# pocketbone.net
KiCad netlist of a schematic drawn in EAGLE
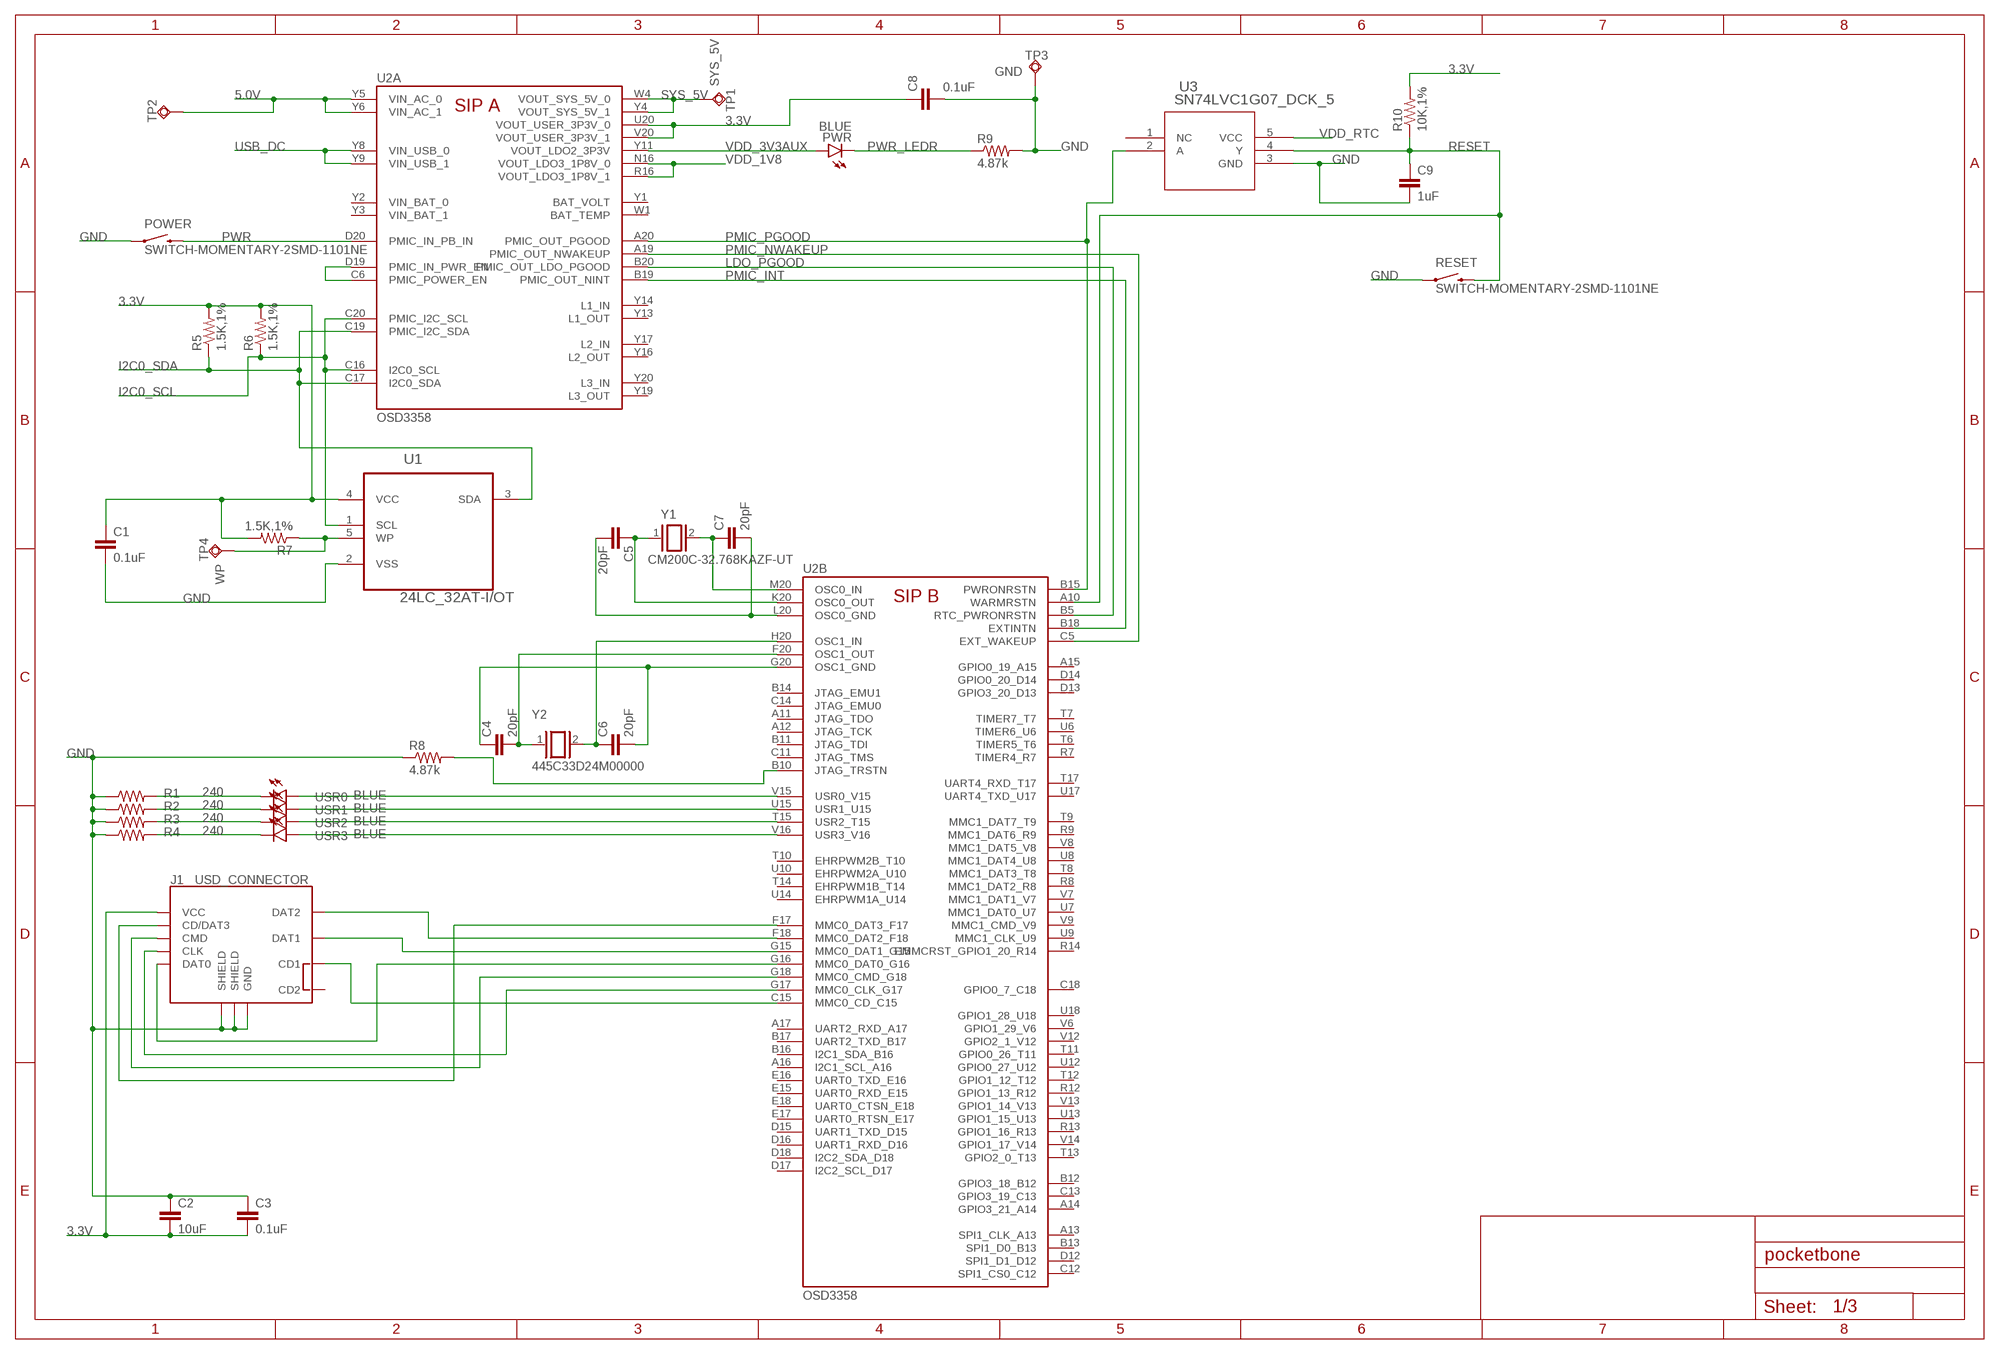
[diagram p0: schematic, sheet 1]
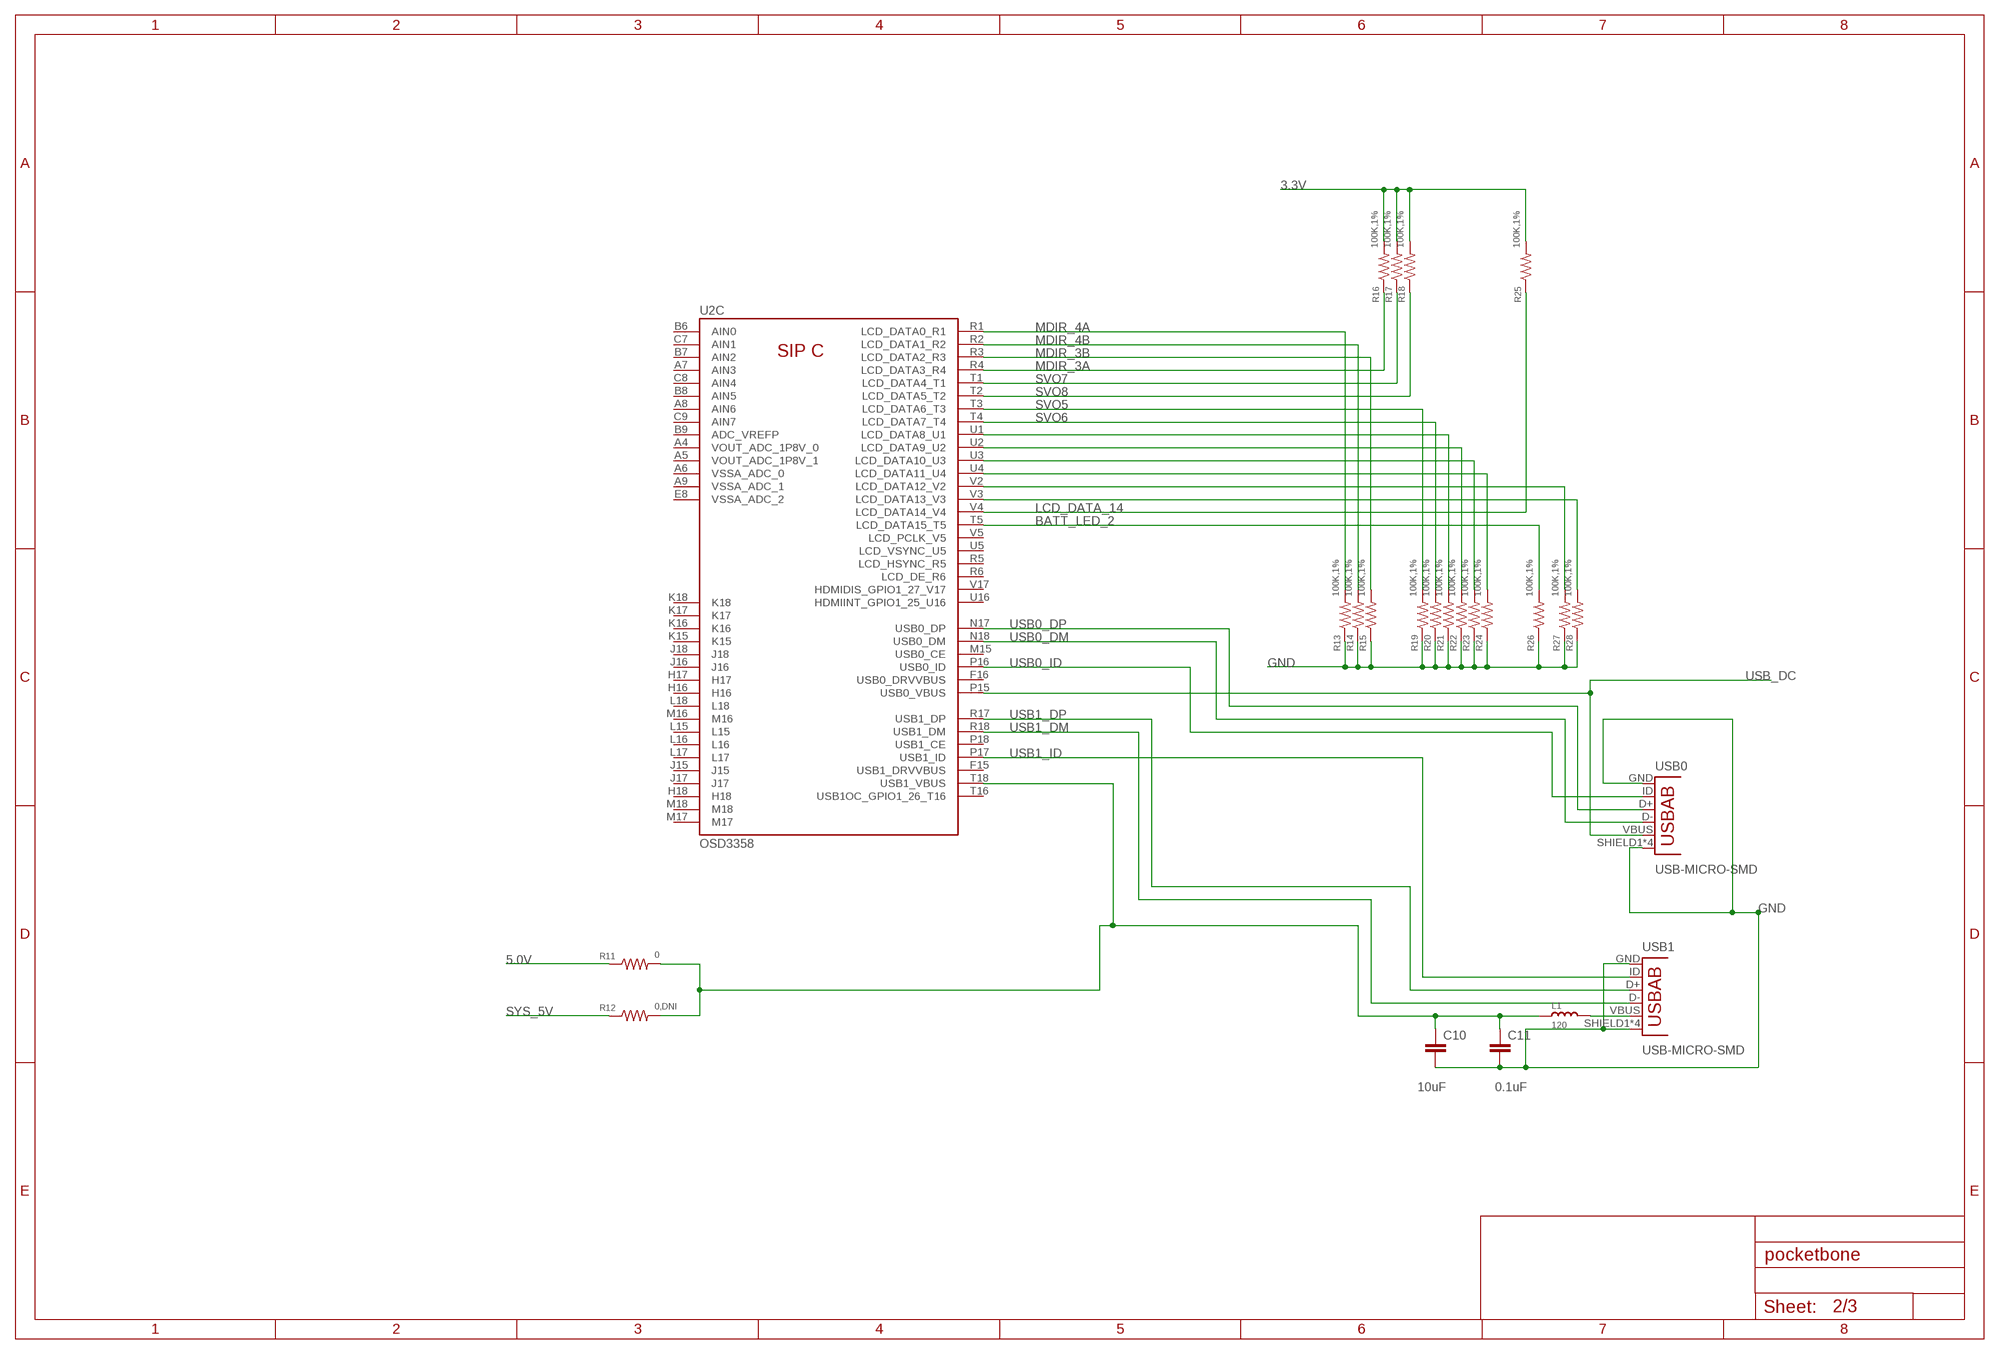
[diagram p1: schematic, sheet 2]
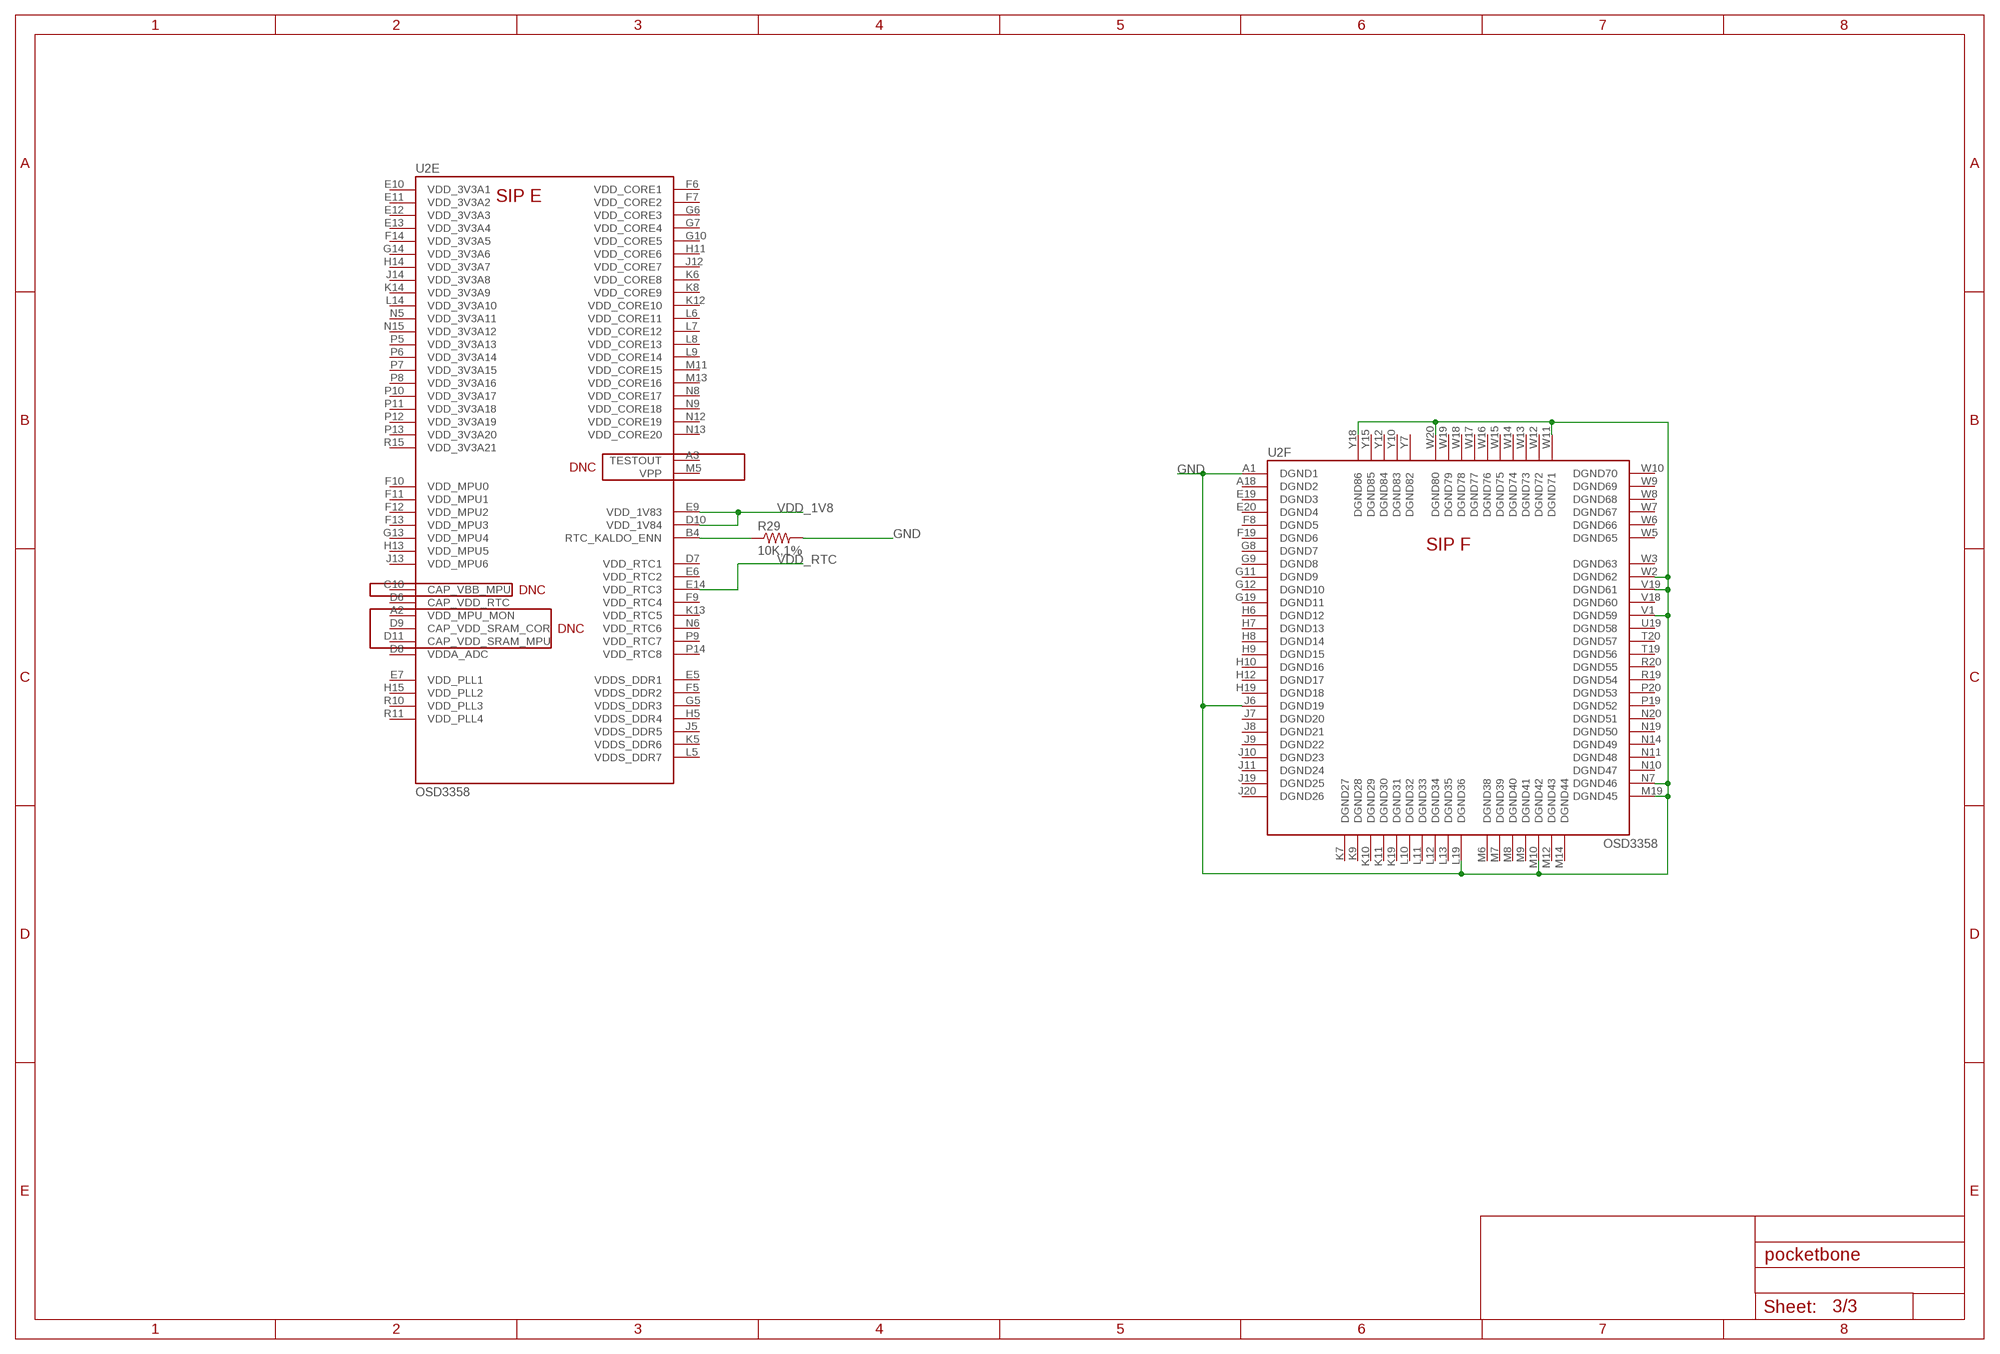
[diagram p2: schematic, sheet 3]

(export (version "E")
  (design (tool "Eeschema 10.0.6"))
  (components
    (comp (ref "C10")
      (value "10uF")
      (footprint "eagle-import:0805")
      (libsource (lib "eagle-import") (part "CAP0805"))
    )
    (comp (ref "C11")
      (value "0.1uF")
      (footprint "eagle-import:0402-CAP")
      (libsource (lib "eagle-import") (part "CAP0402-CAP"))
    )
    (comp (ref "L1")
      (value "120")
      (footprint "eagle-import:L0603")
      (libsource (lib "eagle-import") (part "INDUCTOR/FERRITE-BEAD'0603'"))
    )
    (comp (ref "R11")
      (value "0")
      (footprint "eagle-import:0402-RES")
      (libsource (lib "eagle-import") (part "RESISTOR0402-RES"))
    )
    (comp (ref "R12")
      (value "0,DNI")
      (footprint "eagle-import:0402-RES")
      (libsource (lib "eagle-import") (part "RESISTOR0402-RES"))
    )
    (comp (ref "R13")
      (value "100K,1%")
      (footprint "eagle-import:0402-RES")
      (libsource (lib "eagle-import") (part "RESISTOR0402-RES"))
    )
    (comp (ref "R14")
      (value "100K,1%")
      (footprint "eagle-import:0402-RES")
      (libsource (lib "eagle-import") (part "RESISTOR0402-RES"))
    )
    (comp (ref "R15")
      (value "100K,1%")
      (footprint "eagle-import:0402-RES")
      (libsource (lib "eagle-import") (part "RESISTOR0402-RES"))
    )
    (comp (ref "R16")
      (value "100K,1%")
      (footprint "eagle-import:0402-RES")
      (libsource (lib "eagle-import") (part "RESISTOR0402-RES"))
    )
    (comp (ref "R17")
      (value "100K,1%")
      (footprint "eagle-import:0402-RES")
      (libsource (lib "eagle-import") (part "RESISTOR0402-RES"))
    )
    (comp (ref "R18")
      (value "100K,1%")
      (footprint "eagle-import:0402-RES")
      (libsource (lib "eagle-import") (part "RESISTOR0402-RES"))
    )
    (comp (ref "R19")
      (value "100K,1%")
      (footprint "eagle-import:0402-RES")
      (libsource (lib "eagle-import") (part "RESISTOR0402-RES"))
    )
    (comp (ref "R20")
      (value "100K,1%")
      (footprint "eagle-import:0402-RES")
      (libsource (lib "eagle-import") (part "RESISTOR0402-RES"))
    )
    (comp (ref "R21")
      (value "100K,1%")
      (footprint "eagle-import:0402-RES")
      (libsource (lib "eagle-import") (part "RESISTOR0402-RES"))
    )
    (comp (ref "R22")
      (value "100K,1%")
      (footprint "eagle-import:0402-RES")
      (libsource (lib "eagle-import") (part "RESISTOR0402-RES"))
    )
    (comp (ref "R23")
      (value "100K,1%")
      (footprint "eagle-import:0402-RES")
      (libsource (lib "eagle-import") (part "RESISTOR0402-RES"))
    )
    (comp (ref "R24")
      (value "100K,1%")
      (footprint "eagle-import:0402-RES")
      (libsource (lib "eagle-import") (part "RESISTOR0402-RES"))
    )
    (comp (ref "R25")
      (value "100K,1%")
      (footprint "eagle-import:0402-RES")
      (libsource (lib "eagle-import") (part "RESISTOR0402-RES"))
    )
    (comp (ref "R26")
      (value "100K,1%")
      (footprint "eagle-import:0402-RES")
      (libsource (lib "eagle-import") (part "RESISTOR0402-RES"))
    )
    (comp (ref "R27")
      (value "100K,1%")
      (footprint "eagle-import:0402-RES")
      (libsource (lib "eagle-import") (part "RESISTOR0402-RES"))
    )
    (comp (ref "R28")
      (value "100K,1%")
      (footprint "eagle-import:0402-RES")
      (libsource (lib "eagle-import") (part "RESISTOR0402-RES"))
    )
    (comp (ref "U2")
      (value "OSD3358")
      (footprint "eagle-import:OSD3358")
      (libsource (lib "eagle-import") (part "OSD3358"))
    )
    (comp (ref "USB0")
      (value "USB-MICRO-SMD")
      (footprint "eagle-import:USB-AB-MICRO-SMD")
      (libsource (lib "eagle-import") (part "USB-AB"))
    )
    (comp (ref "USB1")
      (value "USB-MICRO-SMD")
      (footprint "eagle-import:USB-AB-MICRO-SMD")
      (libsource (lib "eagle-import") (part "USB-AB"))
    )
    (comp (ref "C1")
      (value "0.1uF")
      (footprint "eagle-import:0402-CAP")
      (libsource (lib "eagle-import") (part "CAP0402-CAP"))
    )
    (comp (ref "C2")
      (value "10uF")
      (footprint "eagle-import:0805")
      (libsource (lib "eagle-import") (part "CAP0805"))
    )
    (comp (ref "C3")
      (value "0.1uF")
      (footprint "eagle-import:0402-CAP")
      (libsource (lib "eagle-import") (part "CAP0402-CAP"))
    )
    (comp (ref "C4")
      (value "20pF")
      (footprint "eagle-import:0402-CAP")
      (libsource (lib "eagle-import") (part "CAP0402-CAP"))
    )
    (comp (ref "C5")
      (value "20pF")
      (footprint "eagle-import:0402-CAP")
      (libsource (lib "eagle-import") (part "CAP0402-CAP"))
    )
    (comp (ref "C6")
      (value "20pF")
      (footprint "eagle-import:0402-CAP")
      (libsource (lib "eagle-import") (part "CAP0402-CAP"))
    )
    (comp (ref "C7")
      (value "20pF")
      (footprint "eagle-import:0402-CAP")
      (libsource (lib "eagle-import") (part "CAP0402-CAP"))
    )
    (comp (ref "C8")
      (value "0.1uF")
      (footprint "eagle-import:0402-CAP")
      (libsource (lib "eagle-import") (part "CAP0402-CAP"))
    )
    (comp (ref "C9")
      (value "1uF")
      (footprint "eagle-import:0402-CAP")
      (libsource (lib "eagle-import") (part "CAP0402-CAP"))
    )
    (comp (ref "J1")
      (value "USD_CONNECTOR")
      (footprint "eagle-import:MICRO-SD-SOCKET-PP")
      (libsource (lib "eagle-import") (part "USD_CONNECTOR"))
    )
    (comp (ref "POWER")
      (value "SWITCH-MOMENTARY-2SMD-1101NE")
      (footprint "eagle-import:TACTILE-SWITCH-1101NE")
      (libsource (lib "eagle-import") (part "SWITCH-MOMENTARY-2SMD-1101NE"))
    )
    (comp (ref "PWR")
      (value "BLUE")
      (footprint "eagle-import:LED-0603")
      (libsource (lib "eagle-import") (part "LED0603"))
    )
    (comp (ref "R1")
      (value "240")
      (footprint "eagle-import:0402-RES")
      (libsource (lib "eagle-import") (part "RESISTOR0402-RES"))
    )
    (comp (ref "R2")
      (value "240")
      (footprint "eagle-import:0402-RES")
      (libsource (lib "eagle-import") (part "RESISTOR0402-RES"))
    )
    (comp (ref "R3")
      (value "240")
      (footprint "eagle-import:0402-RES")
      (libsource (lib "eagle-import") (part "RESISTOR0402-RES"))
    )
    (comp (ref "R4")
      (value "240")
      (footprint "eagle-import:0402-RES")
      (libsource (lib "eagle-import") (part "RESISTOR0402-RES"))
    )
    (comp (ref "R5")
      (value "1.5K,1%")
      (footprint "eagle-import:0402-RES")
      (libsource (lib "eagle-import") (part "RESISTOR0402-RES"))
    )
    (comp (ref "R6")
      (value "1.5K,1%")
      (footprint "eagle-import:0402-RES")
      (libsource (lib "eagle-import") (part "RESISTOR0402-RES"))
    )
    (comp (ref "R7")
      (value "1.5K,1%")
      (footprint "eagle-import:0402-RES")
      (libsource (lib "eagle-import") (part "RESISTOR0402-RES"))
    )
    (comp (ref "R8")
      (value "4.87k")
      (footprint "eagle-import:0402-RES")
      (libsource (lib "eagle-import") (part "RESISTOR0402-RES"))
    )
    (comp (ref "R9")
      (value "4.87k")
      (footprint "eagle-import:0402-RES")
      (libsource (lib "eagle-import") (part "RESISTOR0402-RES"))
    )
    (comp (ref "R10")
      (value "10K,1%")
      (footprint "eagle-import:0402-RES")
      (libsource (lib "eagle-import") (part "RESISTOR0402-RES"))
    )
    (comp (ref "RESET")
      (value "SWITCH-MOMENTARY-2SMD-1101NE")
      (footprint "eagle-import:TACTILE-SWITCH-1101NE")
      (libsource (lib "eagle-import") (part "SWITCH-MOMENTARY-2SMD-1101NE"))
    )
    (comp (ref "TP1")
      (value "TPSQPAD1-17")
      (footprint "eagle-import:P1-17")
      (fields (field (name "TP_SIGNAL_NAME") "SYS_5V"))
      (libsource (lib "eagle-import") (part "TPSQPAD1-17"))
    )
    (comp (ref "TP2")
      (value "TPSQPAD1-17")
      (footprint "eagle-import:P1-17")
      (fields (field (name "TP_SIGNAL_NAME") "5.0V"))
      (libsource (lib "eagle-import") (part "TPSQPAD1-17"))
    )
    (comp (ref "TP3")
      (value "TPSQPAD1-17")
      (footprint "eagle-import:P1-17")
      (fields (field (name "TP_SIGNAL_NAME") "GND"))
      (libsource (lib "eagle-import") (part "TPSQPAD1-17"))
    )
    (comp (ref "TP4")
      (value "TPSQPAD1-17")
      (footprint "eagle-import:P1-17")
      (fields (field (name "TP_SIGNAL_NAME") "WP"))
      (libsource (lib "eagle-import") (part "TPSQPAD1-17"))
    )
    (comp (ref "U1")
      (value "24LC_32AT-I/OT")
      (footprint "eagle-import:SOT95P290X145-5N")
      (fields (field (name "MPN") "24LC32AT-I/OT"))
      (libsource (lib "eagle-import") (part "24LC_32AT-I/OT"))
    )
    (comp (ref "U3")
      (value "SN74LVC1G07_DCK_5")
      (footprint "eagle-import:DCK5")
      (fields
        (field (name "GENERIC_PART_NUMBER") "SN74LVC1G07")
        (field (name "MANUFACTURER") "Texas Instruments")
        (field (name "MANUFACTURER_PART_NUMBER") "sn74lvc1g07_dck_5")
      )
      (libsource (lib "eagle-import") (part "SN74LVC1G07_DCK_5"))
    )
    (comp (ref "USR0")
      (value "BLUE")
      (footprint "eagle-import:LED-0603")
      (libsource (lib "eagle-import") (part "LED0603"))
    )
    (comp (ref "USR1")
      (value "BLUE")
      (footprint "eagle-import:LED-0603")
      (libsource (lib "eagle-import") (part "LED0603"))
    )
    (comp (ref "USR2")
      (value "BLUE")
      (footprint "eagle-import:LED-0603")
      (libsource (lib "eagle-import") (part "LED0603"))
    )
    (comp (ref "USR3")
      (value "BLUE")
      (footprint "eagle-import:LED-0603")
      (libsource (lib "eagle-import") (part "LED0603"))
    )
    (comp (ref "Y1")
      (value "CM200C-32.768KAZF-UT")
      (footprint "eagle-import:CM200C-32.768KAZF-UT")
      (libsource (lib "eagle-import") (part "CM200C-32.768KAZF-UT"))
    )
    (comp (ref "Y2")
      (value "445C33D24M00000")
      (footprint "eagle-import:445C33D24M00000")
      (libsource (lib "eagle-import") (part "445C33D24M00000"))
    )
    (comp (ref "R29")
      (value "10K,1%")
      (footprint "eagle-import:0402-RES")
      (libsource (lib "eagle-import") (part "RESISTOR0402-RES"))
    )
  )
  (nets
    (net (code "1") (name "3.3V") (class "Default")
      (node (ref "C1") (pin "1") (pinfunction "1_1") (pintype "passive"))
      (node (ref "C2") (pin "2") (pinfunction "2_2") (pintype "passive"))
      (node (ref "C3") (pin "2") (pinfunction "2_2") (pintype "passive"))
      (node (ref "C8") (pin "1") (pinfunction "1_1") (pintype "passive"))
      (node (ref "J1") (pin "VCC") (pinfunction "VCC_VCC") (pintype "bidirectional"))
      (node (ref "R10") (pin "2") (pinfunction "2_2") (pintype "passive"))
      (node (ref "R16") (pin "2") (pinfunction "2_2") (pintype "passive"))
      (node (ref "R17") (pin "2") (pinfunction "2_2") (pintype "passive"))
      (node (ref "R18") (pin "2") (pinfunction "2_2") (pintype "passive"))
      (node (ref "R25") (pin "2") (pinfunction "2_2") (pintype "passive"))
      (node (ref "R5") (pin "2") (pinfunction "2_2") (pintype "passive"))
      (node (ref "R6") (pin "2") (pinfunction "2_2") (pintype "passive"))
      (node (ref "R7") (pin "2") (pinfunction "2_2") (pintype "passive"))
      (node (ref "U1") (pin "4") (pinfunction "VCC_4") (pintype "power_in"))
      (node (ref "U2") (pin "U20") (pinfunction "VOUT_USER_3P3V_0_U20") (pintype "power_in"))
      (node (ref "U2") (pin "V20") (pinfunction "VOUT_USER_3P3V_1_V20") (pintype "power_in"))
    )
    (net (code "2") (name "5.0V") (class "Default")
      (node (ref "R11") (pin "1") (pinfunction "1_1") (pintype "passive"))
      (node (ref "TP2") (pin "TP") (pinfunction "TP_TP") (pintype "input"))
      (node (ref "U2") (pin "Y5") (pinfunction "VIN_AC_0_Y5") (pintype "power_in"))
      (node (ref "U2") (pin "Y6") (pinfunction "VIN_AC_1_Y6") (pintype "power_in"))
    )
    (net (code "3") (name "BATT_LED_2") (class "Default")
      (node (ref "R26") (pin "2") (pinfunction "2_2") (pintype "passive"))
      (node (ref "U2") (pin "T5") (pinfunction "LCD_DATA15_T5_T5") (pintype "bidirectional"))
    )
    (net (code "4") (name "GND") (class "Default")
      (node (ref "C1") (pin "2") (pinfunction "2_2") (pintype "passive"))
      (node (ref "C10") (pin "2") (pinfunction "2_2") (pintype "passive"))
      (node (ref "C11") (pin "2") (pinfunction "2_2") (pintype "passive"))
      (node (ref "C2") (pin "1") (pinfunction "1_1") (pintype "passive"))
      (node (ref "C3") (pin "1") (pinfunction "1_1") (pintype "passive"))
      (node (ref "C8") (pin "2") (pinfunction "2_2") (pintype "passive"))
      (node (ref "C9") (pin "2") (pinfunction "2_2") (pintype "passive"))
      (node (ref "J1") (pin "GND") (pinfunction "GND_GND") (pintype "bidirectional"))
      (node (ref "J1") (pin "GND1") (pinfunction "SHIELD_GND1") (pintype "bidirectional"))
      (node (ref "J1") (pin "GND3") (pinfunction "SHIELD_GND3") (pintype "bidirectional"))
      (node (ref "POWER") (pin "1") (pinfunction "1_1") (pintype "passive"))
      (node (ref "R1") (pin "1") (pinfunction "1_1") (pintype "passive"))
      (node (ref "R13") (pin "1") (pinfunction "1_1") (pintype "passive"))
      (node (ref "R14") (pin "1") (pinfunction "1_1") (pintype "passive"))
      (node (ref "R15") (pin "1") (pinfunction "1_1") (pintype "passive"))
      (node (ref "R19") (pin "1") (pinfunction "1_1") (pintype "passive"))
      (node (ref "R2") (pin "1") (pinfunction "1_1") (pintype "passive"))
      (node (ref "R20") (pin "1") (pinfunction "1_1") (pintype "passive"))
      (node (ref "R21") (pin "1") (pinfunction "1_1") (pintype "passive"))
      (node (ref "R22") (pin "1") (pinfunction "1_1") (pintype "passive"))
      (node (ref "R23") (pin "1") (pinfunction "1_1") (pintype "passive"))
      (node (ref "R24") (pin "1") (pinfunction "1_1") (pintype "passive"))
      (node (ref "R26") (pin "1") (pinfunction "1_1") (pintype "passive"))
      (node (ref "R27") (pin "1") (pinfunction "1_1") (pintype "passive"))
      (node (ref "R28") (pin "1") (pinfunction "1_1") (pintype "passive"))
      (node (ref "R29") (pin "2") (pinfunction "2_2") (pintype "passive"))
      (node (ref "R3") (pin "1") (pinfunction "1_1") (pintype "passive"))
      (node (ref "R4") (pin "1") (pinfunction "1_1") (pintype "passive"))
      (node (ref "R8") (pin "1") (pinfunction "1_1") (pintype "passive"))
      (node (ref "R9") (pin "2") (pinfunction "2_2") (pintype "passive"))
      (node (ref "RESET") (pin "1") (pinfunction "1_1") (pintype "passive"))
      (node (ref "TP3") (pin "TP") (pinfunction "TP_TP") (pintype "input"))
      (node (ref "U1") (pin "2") (pinfunction "VSS_2") (pintype "passive"))
      (node (ref "U2") (pin "A1") (pinfunction "DGND1_A1") (pintype "bidirectional"))
      (node (ref "U2") (pin "J6") (pinfunction "DGND19_J6") (pintype "bidirectional"))
      (node (ref "U2") (pin "L19") (pinfunction "DGND36_L19") (pintype "bidirectional"))
      (node (ref "U2") (pin "M10") (pinfunction "DGND42_M10") (pintype "bidirectional"))
      (node (ref "U2") (pin "M19") (pinfunction "DGND45_M19") (pintype "bidirectional"))
      (node (ref "U2") (pin "N7") (pinfunction "DGND46_N7") (pintype "bidirectional"))
      (node (ref "U2") (pin "V1") (pinfunction "DGND59_V1") (pintype "bidirectional"))
      (node (ref "U2") (pin "V19") (pinfunction "DGND61_V19") (pintype "bidirectional"))
      (node (ref "U2") (pin "W11") (pinfunction "DGND71_W11") (pintype "bidirectional"))
      (node (ref "U2") (pin "W2") (pinfunction "DGND62_W2") (pintype "bidirectional"))
      (node (ref "U2") (pin "W20") (pinfunction "DGND80_W20") (pintype "bidirectional"))
      (node (ref "U2") (pin "Y18") (pinfunction "DGND86_Y18") (pintype "bidirectional"))
      (node (ref "U3") (pin "3") (pinfunction "GND_3") (pintype "power_in"))
      (node (ref "USB0") (pin "GND") (pinfunction "GND_GND") (pintype "bidirectional"))
      (node (ref "USB0") (pin "SHIELD1") (pinfunction "SHIELD_SHIELD1") (pintype "bidirectional"))
      (node (ref "USB0") (pin "SHIELD2") (pinfunction "SHIELD_SHIELD2") (pintype "bidirectional"))
      (node (ref "USB0") (pin "SHIELD3") (pinfunction "SHIELD_SHIELD3") (pintype "bidirectional"))
      (node (ref "USB0") (pin "SHIELD4") (pinfunction "SHIELD_SHIELD4") (pintype "bidirectional"))
      (node (ref "USB1") (pin "GND") (pinfunction "GND_GND") (pintype "bidirectional"))
      (node (ref "USB1") (pin "SHIELD1") (pinfunction "SHIELD_SHIELD1") (pintype "bidirectional"))
      (node (ref "USB1") (pin "SHIELD2") (pinfunction "SHIELD_SHIELD2") (pintype "bidirectional"))
      (node (ref "USB1") (pin "SHIELD3") (pinfunction "SHIELD_SHIELD3") (pintype "bidirectional"))
      (node (ref "USB1") (pin "SHIELD4") (pinfunction "SHIELD_SHIELD4") (pintype "bidirectional"))
    )
    (net (code "5") (name "I2C0_SCL") (class "Default")
      (node (ref "R6") (pin "1") (pinfunction "1_1") (pintype "passive"))
      (node (ref "U1") (pin "1") (pinfunction "SCL_1") (pintype "input"))
      (node (ref "U2") (pin "C16") (pinfunction "I2C0_SCL_C16") (pintype "bidirectional"))
      (node (ref "U2") (pin "C20") (pinfunction "PMIC_I2C_SCL_C20") (pintype "bidirectional"))
    )
    (net (code "6") (name "I2C0_SDA") (class "Default")
      (node (ref "R5") (pin "1") (pinfunction "1_1") (pintype "passive"))
      (node (ref "U1") (pin "3") (pinfunction "SDA_3") (pintype "bidirectional"))
      (node (ref "U2") (pin "C17") (pinfunction "I2C0_SDA_C17") (pintype "bidirectional"))
      (node (ref "U2") (pin "C19") (pinfunction "PMIC_I2C_SDA_C19") (pintype "bidirectional"))
    )
    (net (code "7") (name "LCD_DATA_14") (class "Default")
      (node (ref "R25") (pin "1") (pinfunction "1_1") (pintype "passive"))
      (node (ref "U2") (pin "V4") (pinfunction "LCD_DATA14_V4_V4") (pintype "bidirectional"))
    )
    (net (code "8") (name "LDO_PGOOD") (class "Default")
      (node (ref "U2") (pin "B20") (pinfunction "PMIC_OUT_LDO_PGOOD_B20") (pintype "output"))
      (node (ref "U2") (pin "B5") (pinfunction "RTC_PWRONRSTN_B5") (pintype "bidirectional"))
    )
    (net (code "9") (name "MDIR_3A") (class "Default")
      (node (ref "R16") (pin "1") (pinfunction "1_1") (pintype "passive"))
      (node (ref "U2") (pin "R4") (pinfunction "LCD_DATA3_R4_R4") (pintype "bidirectional"))
    )
    (net (code "10") (name "MDIR_3B") (class "Default")
      (node (ref "R15") (pin "2") (pinfunction "2_2") (pintype "passive"))
      (node (ref "U2") (pin "R3") (pinfunction "LCD_DATA2_R3_R3") (pintype "bidirectional"))
    )
    (net (code "11") (name "MDIR_4A") (class "Default")
      (node (ref "R13") (pin "2") (pinfunction "2_2") (pintype "passive"))
      (node (ref "U2") (pin "R1") (pinfunction "LCD_DATA0_R1_R1") (pintype "bidirectional"))
    )
    (net (code "12") (name "MDIR_4B") (class "Default")
      (node (ref "R14") (pin "2") (pinfunction "2_2") (pintype "passive"))
      (node (ref "U2") (pin "R2") (pinfunction "LCD_DATA1_R2_R2") (pintype "bidirectional"))
    )
    (net (code "13") (name "Net-(L1-Pad2)") (class "Default")
      (node (ref "L1") (pin "2") (pinfunction "2_2") (pintype "passive"))
      (node (ref "USB1") (pin "VBUS") (pinfunction "VBUS_VBUS") (pintype "bidirectional"))
    )
    (net (code "14") (name "Net-(R1-Pad2)") (class "Default")
      (node (ref "R1") (pin "2") (pinfunction "2_2") (pintype "passive"))
      (node (ref "USR0") (pin "C") (pinfunction "C_C") (pintype "passive"))
    )
    (net (code "15") (name "Net-(R2-Pad2)") (class "Default")
      (node (ref "R2") (pin "2") (pinfunction "2_2") (pintype "passive"))
      (node (ref "USR1") (pin "C") (pinfunction "C_C") (pintype "passive"))
    )
    (net (code "16") (name "Net-(R3-Pad2)") (class "Default")
      (node (ref "R3") (pin "2") (pinfunction "2_2") (pintype "passive"))
      (node (ref "USR2") (pin "C") (pinfunction "C_C") (pintype "passive"))
    )
    (net (code "17") (name "Net-(R4-Pad2)") (class "Default")
      (node (ref "R4") (pin "2") (pinfunction "2_2") (pintype "passive"))
      (node (ref "USR3") (pin "C") (pinfunction "C_C") (pintype "passive"))
    )
    (net (code "18") (name "Net-(U1-WP)") (class "Default")
      (node (ref "R7") (pin "1") (pinfunction "1_1") (pintype "passive"))
      (node (ref "TP4") (pin "TP") (pinfunction "TP_TP") (pintype "input"))
      (node (ref "U1") (pin "5") (pinfunction "WP_5") (pintype "input"))
    )
    (net (code "19") (name "Net-(U2A-PMIC_IN_PWR_EN)") (class "Default")
      (node (ref "U2") (pin "C6") (pinfunction "PMIC_POWER_EN_C6") (pintype "output"))
      (node (ref "U2") (pin "D19") (pinfunction "PMIC_IN_PWR_EN_D19") (pintype "input"))
    )
    (net (code "20") (name "Net-(U2B-JTAG_TRSTN)") (class "Default")
      (node (ref "R8") (pin "2") (pinfunction "2_2") (pintype "passive"))
      (node (ref "U2") (pin "B10") (pinfunction "JTAG_TRSTN_B10") (pintype "bidirectional"))
    )
    (net (code "21") (name "Net-(U2B-MMC0_CD_C15)") (class "Default")
      (node (ref "J1") (pin "CD1") (pinfunction "CD1_CD1") (pintype "bidirectional"))
      (node (ref "U2") (pin "C15") (pinfunction "MMC0_CD_C15_C15") (pintype "bidirectional"))
    )
    (net (code "22") (name "Net-(U2B-MMC0_CLK_G17)") (class "Default")
      (node (ref "J1") (pin "CLK") (pinfunction "CLK_CLK") (pintype "bidirectional"))
      (node (ref "U2") (pin "G17") (pinfunction "MMC0_CLK_G17_G17") (pintype "bidirectional"))
    )
    (net (code "23") (name "Net-(U2B-MMC0_CMD_G18)") (class "Default")
      (node (ref "J1") (pin "CMD") (pinfunction "CMD_CMD") (pintype "bidirectional"))
      (node (ref "U2") (pin "G18") (pinfunction "MMC0_CMD_G18_G18") (pintype "bidirectional"))
    )
    (net (code "24") (name "Net-(U2B-MMC0_DAT0_G16)") (class "Default")
      (node (ref "J1") (pin "DAT0") (pinfunction "DAT0_DAT0") (pintype "bidirectional"))
      (node (ref "U2") (pin "G16") (pinfunction "MMC0_DAT0_G16_G16") (pintype "bidirectional"))
    )
    (net (code "25") (name "Net-(U2B-MMC0_DAT1_G15)") (class "Default")
      (node (ref "J1") (pin "DAT1") (pinfunction "DAT1_DAT1") (pintype "bidirectional"))
      (node (ref "U2") (pin "G15") (pinfunction "MMC0_DAT1_G15_G15") (pintype "bidirectional"))
    )
    (net (code "26") (name "Net-(U2B-MMC0_DAT2_F18)") (class "Default")
      (node (ref "J1") (pin "DAT2") (pinfunction "DAT2_DAT2") (pintype "bidirectional"))
      (node (ref "U2") (pin "F18") (pinfunction "MMC0_DAT2_F18_F18") (pintype "bidirectional"))
    )
    (net (code "27") (name "Net-(U2B-MMC0_DAT3_F17)") (class "Default")
      (node (ref "J1") (pin "CD/DAT3") (pinfunction "CD/DAT3_CD/DAT3") (pintype "bidirectional"))
      (node (ref "U2") (pin "F17") (pinfunction "MMC0_DAT3_F17_F17") (pintype "bidirectional"))
    )
    (net (code "28") (name "Net-(U2B-OSC0_GND)") (class "Default")
      (node (ref "C5") (pin "2") (pinfunction "2_2") (pintype "passive"))
      (node (ref "C7") (pin "2") (pinfunction "2_2") (pintype "passive"))
      (node (ref "U2") (pin "L20") (pinfunction "OSC0_GND_L20") (pintype "bidirectional"))
    )
    (net (code "29") (name "Net-(U2B-OSC0_IN)") (class "Default")
      (node (ref "C7") (pin "1") (pinfunction "1_1") (pintype "passive"))
      (node (ref "U2") (pin "M20") (pinfunction "OSC0_IN_M20") (pintype "bidirectional"))
      (node (ref "Y1") (pin "2") (pinfunction "2_2") (pintype "passive"))
    )
    (net (code "30") (name "Net-(U2B-OSC0_OUT)") (class "Default")
      (node (ref "C5") (pin "1") (pinfunction "1_1") (pintype "passive"))
      (node (ref "U2") (pin "K20") (pinfunction "OSC0_OUT_K20") (pintype "bidirectional"))
      (node (ref "Y1") (pin "1") (pinfunction "1_1") (pintype "passive"))
    )
    (net (code "31") (name "Net-(U2B-OSC1_GND)") (class "Default")
      (node (ref "C4") (pin "1") (pinfunction "1_1") (pintype "passive"))
      (node (ref "C6") (pin "2") (pinfunction "2_2") (pintype "passive"))
      (node (ref "U2") (pin "G20") (pinfunction "OSC1_GND_G20") (pintype "bidirectional"))
    )
    (net (code "32") (name "Net-(U2B-OSC1_IN)") (class "Default")
      (node (ref "C6") (pin "1") (pinfunction "1_1") (pintype "passive"))
      (node (ref "U2") (pin "H20") (pinfunction "OSC1_IN_H20") (pintype "bidirectional"))
      (node (ref "Y2") (pin "2") (pinfunction "2_2") (pintype "passive"))
    )
    (net (code "33") (name "Net-(U2B-OSC1_OUT)") (class "Default")
      (node (ref "C4") (pin "2") (pinfunction "2_2") (pintype "passive"))
      (node (ref "U2") (pin "F20") (pinfunction "OSC1_OUT_F20") (pintype "bidirectional"))
      (node (ref "Y2") (pin "1") (pinfunction "1_1") (pintype "passive"))
    )
    (net (code "34") (name "Net-(U2B-USR0_V15)") (class "Default")
      (node (ref "U2") (pin "V15") (pinfunction "USR0_V15_V15") (pintype "bidirectional"))
      (node (ref "USR0") (pin "A") (pinfunction "A_A") (pintype "passive"))
    )
    (net (code "35") (name "Net-(U2B-USR1_U15)") (class "Default")
      (node (ref "U2") (pin "U15") (pinfunction "USR1_U15_U15") (pintype "bidirectional"))
      (node (ref "USR1") (pin "A") (pinfunction "A_A") (pintype "passive"))
    )
    (net (code "36") (name "Net-(U2B-USR2_T15)") (class "Default")
      (node (ref "U2") (pin "T15") (pinfunction "USR2_T15_T15") (pintype "bidirectional"))
      (node (ref "USR2") (pin "A") (pinfunction "A_A") (pintype "passive"))
    )
    (net (code "37") (name "Net-(U2B-USR3_V16)") (class "Default")
      (node (ref "U2") (pin "V16") (pinfunction "USR3_V16_V16") (pintype "bidirectional"))
      (node (ref "USR3") (pin "A") (pinfunction "A_A") (pintype "passive"))
    )
    (net (code "38") (name "Net-(U2C-LCD_DATA8_U1)") (class "Default")
      (node (ref "R21") (pin "2") (pinfunction "2_2") (pintype "passive"))
      (node (ref "U2") (pin "U1") (pinfunction "LCD_DATA8_U1_U1") (pintype "bidirectional"))
    )
    (net (code "39") (name "Net-(U2C-LCD_DATA9_U2)") (class "Default")
      (node (ref "R22") (pin "2") (pinfunction "2_2") (pintype "passive"))
      (node (ref "U2") (pin "U2") (pinfunction "LCD_DATA9_U2_U2") (pintype "bidirectional"))
    )
    (net (code "40") (name "Net-(U2C-LCD_DATA10_U3)") (class "Default")
      (node (ref "R23") (pin "2") (pinfunction "2_2") (pintype "passive"))
      (node (ref "U2") (pin "U3") (pinfunction "LCD_DATA10_U3_U3") (pintype "bidirectional"))
    )
    (net (code "41") (name "Net-(U2C-LCD_DATA11_U4)") (class "Default")
      (node (ref "R24") (pin "2") (pinfunction "2_2") (pintype "passive"))
      (node (ref "U2") (pin "U4") (pinfunction "LCD_DATA11_U4_U4") (pintype "bidirectional"))
    )
    (net (code "42") (name "Net-(U2C-LCD_DATA12_V2)") (class "Default")
      (node (ref "R27") (pin "2") (pinfunction "2_2") (pintype "passive"))
      (node (ref "U2") (pin "V2") (pinfunction "LCD_DATA12_V2_V2") (pintype "bidirectional"))
    )
    (net (code "43") (name "Net-(U2C-LCD_DATA13_V3)") (class "Default")
      (node (ref "R28") (pin "2") (pinfunction "2_2") (pintype "passive"))
      (node (ref "U2") (pin "V3") (pinfunction "LCD_DATA13_V3_V3") (pintype "bidirectional"))
    )
    (net (code "44") (name "Net-(U2C-USB1_VBUS)") (class "Default")
      (node (ref "C10") (pin "1") (pinfunction "1_1") (pintype "passive"))
      (node (ref "C11") (pin "1") (pinfunction "1_1") (pintype "passive"))
      (node (ref "L1") (pin "1") (pinfunction "1_1") (pintype "passive"))
      (node (ref "R11") (pin "2") (pinfunction "2_2") (pintype "passive"))
      (node (ref "R12") (pin "2") (pinfunction "2_2") (pintype "passive"))
      (node (ref "U2") (pin "T18") (pinfunction "USB1_VBUS_T18") (pintype "bidirectional"))
    )
    (net (code "45") (name "Net-(U2E-RTC_KALDO_ENN)") (class "Default")
      (node (ref "R29") (pin "1") (pinfunction "1_1") (pintype "passive"))
      (node (ref "U2") (pin "B4") (pinfunction "RTC_KALDO_ENN_B4") (pintype "bidirectional"))
    )
    (net (code "46") (name "PMIC_INT") (class "Default")
      (node (ref "U2") (pin "B18") (pinfunction "EXTINTN_B18") (pintype "bidirectional"))
      (node (ref "U2") (pin "B19") (pinfunction "PMIC_OUT_NINT_B19") (pintype "output"))
    )
    (net (code "47") (name "PMIC_NWAKEUP") (class "Default")
      (node (ref "U2") (pin "A19") (pinfunction "PMIC_OUT_NWAKEUP_A19") (pintype "output"))
      (node (ref "U2") (pin "C5") (pinfunction "EXT_WAKEUP_C5") (pintype "bidirectional"))
    )
    (net (code "48") (name "PMIC_PGOOD") (class "Default")
      (node (ref "U2") (pin "A20") (pinfunction "PMIC_OUT_PGOOD_A20") (pintype "output"))
      (node (ref "U2") (pin "B15") (pinfunction "PWRONRSTN_B15") (pintype "bidirectional"))
      (node (ref "U3") (pin "2") (pinfunction "A_2") (pintype "input"))
    )
    (net (code "49") (name "PWR") (class "Default")
      (node (ref "POWER") (pin "2") (pinfunction "2_2") (pintype "passive"))
      (node (ref "U2") (pin "D20") (pinfunction "PMIC_IN_PB_IN_D20") (pintype "bidirectional"))
    )
    (net (code "50") (name "PWR_LEDR") (class "Default")
      (node (ref "PWR") (pin "C") (pinfunction "C_C") (pintype "passive"))
      (node (ref "R9") (pin "1") (pinfunction "1_1") (pintype "passive"))
    )
    (net (code "51") (name "RESET") (class "Default")
      (node (ref "C9") (pin "1") (pinfunction "1_1") (pintype "passive"))
      (node (ref "R10") (pin "1") (pinfunction "1_1") (pintype "passive"))
      (node (ref "RESET") (pin "2") (pinfunction "2_2") (pintype "passive"))
      (node (ref "U2") (pin "A10") (pinfunction "WARMRSTN_A10") (pintype "bidirectional"))
      (node (ref "U3") (pin "4") (pinfunction "Y_4") (pintype "output"))
    )
    (net (code "52") (name "SVO5") (class "Default")
      (node (ref "R19") (pin "2") (pinfunction "2_2") (pintype "passive"))
      (node (ref "U2") (pin "T3") (pinfunction "LCD_DATA6_T3_T3") (pintype "bidirectional"))
    )
    (net (code "53") (name "SVO6") (class "Default")
      (node (ref "R20") (pin "2") (pinfunction "2_2") (pintype "passive"))
      (node (ref "U2") (pin "T4") (pinfunction "LCD_DATA7_T4_T4") (pintype "bidirectional"))
    )
    (net (code "54") (name "SVO7") (class "Default")
      (node (ref "R17") (pin "1") (pinfunction "1_1") (pintype "passive"))
      (node (ref "U2") (pin "T1") (pinfunction "LCD_DATA4_T1_T1") (pintype "bidirectional"))
    )
    (net (code "55") (name "SVO8") (class "Default")
      (node (ref "R18") (pin "1") (pinfunction "1_1") (pintype "passive"))
      (node (ref "U2") (pin "T2") (pinfunction "LCD_DATA5_T2_T2") (pintype "bidirectional"))
    )
    (net (code "56") (name "SYS_5V") (class "Default")
      (node (ref "R12") (pin "1") (pinfunction "1_1") (pintype "passive"))
      (node (ref "TP1") (pin "TP") (pinfunction "TP_TP") (pintype "input"))
      (node (ref "U2") (pin "W4") (pinfunction "VOUT_SYS_5V_0_W4") (pintype "power_in"))
      (node (ref "U2") (pin "Y4") (pinfunction "VOUT_SYS_5V_1_Y4") (pintype "power_in"))
    )
    (net (code "57") (name "USB0_DM") (class "Default")
      (node (ref "U2") (pin "N18") (pinfunction "USB0_DM_N18") (pintype "bidirectional"))
      (node (ref "USB0") (pin "D-") (pinfunction "D-_D-") (pintype "bidirectional"))
    )
    (net (code "58") (name "USB0_DP") (class "Default")
      (node (ref "U2") (pin "N17") (pinfunction "USB0_DP_N17") (pintype "bidirectional"))
      (node (ref "USB0") (pin "D+") (pinfunction "D+_D+") (pintype "bidirectional"))
    )
    (net (code "59") (name "USB0_ID") (class "Default")
      (node (ref "U2") (pin "P16") (pinfunction "USB0_ID_P16") (pintype "bidirectional"))
      (node (ref "USB0") (pin "ID") (pinfunction "USBID_ID") (pintype "bidirectional"))
    )
    (net (code "60") (name "USB1_DM") (class "Default")
      (node (ref "U2") (pin "R18") (pinfunction "USB1_DM_R18") (pintype "bidirectional"))
      (node (ref "USB1") (pin "D-") (pinfunction "D-_D-") (pintype "bidirectional"))
    )
    (net (code "61") (name "USB1_DP") (class "Default")
      (node (ref "U2") (pin "R17") (pinfunction "USB1_DP_R17") (pintype "bidirectional"))
      (node (ref "USB1") (pin "D+") (pinfunction "D+_D+") (pintype "bidirectional"))
    )
    (net (code "62") (name "USB1_ID") (class "Default")
      (node (ref "U2") (pin "P17") (pinfunction "USB1_ID_P17") (pintype "bidirectional"))
      (node (ref "USB1") (pin "ID") (pinfunction "USBID_ID") (pintype "bidirectional"))
    )
    (net (code "63") (name "USB_DC") (class "Default")
      (node (ref "U2") (pin "P15") (pinfunction "USB0_VBUS_P15") (pintype "bidirectional"))
      (node (ref "U2") (pin "Y8") (pinfunction "VIN_USB_0_Y8") (pintype "power_in"))
      (node (ref "U2") (pin "Y9") (pinfunction "VIN_USB_1_Y9") (pintype "power_in"))
      (node (ref "USB0") (pin "VBUS") (pinfunction "VBUS_VBUS") (pintype "bidirectional"))
    )
    (net (code "64") (name "VDD_1V8") (class "Default")
      (node (ref "U2") (pin "D10") (pinfunction "VDD_1V84_D10") (pintype "bidirectional"))
      (node (ref "U2") (pin "E9") (pinfunction "VDD_1V83_E9") (pintype "bidirectional"))
      (node (ref "U2") (pin "N16") (pinfunction "VOUT_LDO3_1P8V_0_N16") (pintype "power_in"))
      (node (ref "U2") (pin "R16") (pinfunction "VOUT_LDO3_1P8V_1_R16") (pintype "power_in"))
    )
    (net (code "65") (name "VDD_3V3AUX") (class "Default")
      (node (ref "PWR") (pin "A") (pinfunction "A_A") (pintype "passive"))
      (node (ref "U2") (pin "Y11") (pinfunction "VOUT_LDO2_3P3V_Y11") (pintype "power_in"))
    )
    (net (code "66") (name "VDD_RTC") (class "Default")
      (node (ref "U2") (pin "E14") (pinfunction "VDD_RTC3_E14") (pintype "bidirectional"))
      (node (ref "U3") (pin "5") (pinfunction "VCC_5") (pintype "power_in"))
    )
    (net (code "67") (name "VIN_BAT_0") (class "Default")
      (node (ref "U2") (pin "Y2") (pinfunction "VIN_BAT_0_Y2") (pintype "power_in"))
    )
    (net (code "68") (name "VIN_BAT_1") (class "Default")
      (node (ref "U2") (pin "Y3") (pinfunction "VIN_BAT_1_Y3") (pintype "power_in"))
    )
    (net (code "69") (name "unconnected-(J1-PadCD2)") (class "Default")
      (node (ref "J1") (pin "CD2") (pinfunction "CD2_CD2") (pintype "bidirectional"))
    )
    (net (code "70") (name "unconnected-(U2-PadH16)") (class "Default")
      (node (ref "U2") (pin "H16") (pinfunction "H16_H16") (pintype "bidirectional"))
    )
    (net (code "71") (name "unconnected-(U2-PadH17)") (class "Default")
      (node (ref "U2") (pin "H17") (pinfunction "H17_H17") (pintype "bidirectional"))
    )
    (net (code "72") (name "unconnected-(U2-PadH18)") (class "Default")
      (node (ref "U2") (pin "H18") (pinfunction "H18_H18") (pintype "bidirectional"))
    )
    (net (code "73") (name "unconnected-(U2-PadJ15)") (class "Default")
      (node (ref "U2") (pin "J15") (pinfunction "J15_J15") (pintype "bidirectional"))
    )
    (net (code "74") (name "unconnected-(U2-PadJ16)") (class "Default")
      (node (ref "U2") (pin "J16") (pinfunction "J16_J16") (pintype "bidirectional"))
    )
    (net (code "75") (name "unconnected-(U2-PadJ17)") (class "Default")
      (node (ref "U2") (pin "J17") (pinfunction "J17_J17") (pintype "bidirectional"))
    )
    (net (code "76") (name "unconnected-(U2-PadJ18)") (class "Default")
      (node (ref "U2") (pin "J18") (pinfunction "J18_J18") (pintype "bidirectional"))
    )
    (net (code "77") (name "unconnected-(U2-PadK15)") (class "Default")
      (node (ref "U2") (pin "K15") (pinfunction "K15_K15") (pintype "bidirectional"))
    )
    (net (code "78") (name "unconnected-(U2-PadK16)") (class "Default")
      (node (ref "U2") (pin "K16") (pinfunction "K16_K16") (pintype "bidirectional"))
    )
    (net (code "79") (name "unconnected-(U2-PadK17)") (class "Default")
      (node (ref "U2") (pin "K17") (pinfunction "K17_K17") (pintype "bidirectional"))
    )
    (net (code "80") (name "unconnected-(U2-PadK18)") (class "Default")
      (node (ref "U2") (pin "K18") (pinfunction "K18_K18") (pintype "bidirectional"))
    )
    (net (code "81") (name "unconnected-(U2-PadL15)") (class "Default")
      (node (ref "U2") (pin "L15") (pinfunction "L15_L15") (pintype "bidirectional"))
    )
    (net (code "82") (name "unconnected-(U2-PadL16)") (class "Default")
      (node (ref "U2") (pin "L16") (pinfunction "L16_L16") (pintype "bidirectional"))
    )
    (net (code "83") (name "unconnected-(U2-PadL17)") (class "Default")
      (node (ref "U2") (pin "L17") (pinfunction "L17_L17") (pintype "bidirectional"))
    )
    (net (code "84") (name "unconnected-(U2-PadL18)") (class "Default")
      (node (ref "U2") (pin "L18") (pinfunction "L18_L18") (pintype "bidirectional"))
    )
    (net (code "85") (name "unconnected-(U2-PadM16)") (class "Default")
      (node (ref "U2") (pin "M16") (pinfunction "M16_M16") (pintype "bidirectional"))
    )
    (net (code "86") (name "unconnected-(U2-PadM17)") (class "Default")
      (node (ref "U2") (pin "M17") (pinfunction "M17_M17") (pintype "bidirectional"))
    )
    (net (code "87") (name "unconnected-(U2-PadM18)") (class "Default")
      (node (ref "U2") (pin "M18") (pinfunction "M18_M18") (pintype "bidirectional"))
    )
    (net (code "88") (name "unconnected-(U2A-BAT_TEMP-PadW1)") (class "Default")
      (node (ref "U2") (pin "W1") (pinfunction "BAT_TEMP_W1") (pintype "bidirectional"))
    )
    (net (code "89") (name "unconnected-(U2A-BAT_VOLT-PadY1)") (class "Default")
      (node (ref "U2") (pin "Y1") (pinfunction "BAT_VOLT_Y1") (pintype "bidirectional"))
    )
    (net (code "90") (name "unconnected-(U2A-L1_IN-PadY14)") (class "Default")
      (node (ref "U2") (pin "Y14") (pinfunction "L1_IN_Y14") (pintype "bidirectional"))
    )
    (net (code "91") (name "unconnected-(U2A-L1_OUT-PadY13)") (class "Default")
      (node (ref "U2") (pin "Y13") (pinfunction "L1_OUT_Y13") (pintype "bidirectional"))
    )
    (net (code "92") (name "unconnected-(U2A-L2_IN-PadY17)") (class "Default")
      (node (ref "U2") (pin "Y17") (pinfunction "L2_IN_Y17") (pintype "bidirectional"))
    )
    (net (code "93") (name "unconnected-(U2A-L2_OUT-PadY16)") (class "Default")
      (node (ref "U2") (pin "Y16") (pinfunction "L2_OUT_Y16") (pintype "bidirectional"))
    )
    (net (code "94") (name "unconnected-(U2A-L3_IN-PadY20)") (class "Default")
      (node (ref "U2") (pin "Y20") (pinfunction "L3_IN_Y20") (pintype "bidirectional"))
    )
    (net (code "95") (name "unconnected-(U2A-L3_OUT-PadY19)") (class "Default")
      (node (ref "U2") (pin "Y19") (pinfunction "L3_OUT_Y19") (pintype "bidirectional"))
    )
    (net (code "96") (name "unconnected-(U2B-EHRPWM1A_U14-PadU14)") (class "Default")
      (node (ref "U2") (pin "U14") (pinfunction "EHRPWM1A_U14_U14") (pintype "bidirectional"))
    )
    (net (code "97") (name "unconnected-(U2B-EHRPWM1B_T14-PadT14)") (class "Default")
      (node (ref "U2") (pin "T14") (pinfunction "EHRPWM1B_T14_T14") (pintype "bidirectional"))
    )
    (net (code "98") (name "unconnected-(U2B-EHRPWM2A_U10-PadU10)") (class "Default")
      (node (ref "U2") (pin "U10") (pinfunction "EHRPWM2A_U10_U10") (pintype "bidirectional"))
    )
    (net (code "99") (name "unconnected-(U2B-EHRPWM2B_T10-PadT10)") (class "Default")
      (node (ref "U2") (pin "T10") (pinfunction "EHRPWM2B_T10_T10") (pintype "bidirectional"))
    )
    (net (code "100") (name "unconnected-(U2B-EMMCRST_GPIO1_20_R14-PadR14)") (class "Default")
      (node (ref "U2") (pin "R14") (pinfunction "EMMCRST_GPIO1_20_R14_R14") (pintype "bidirectional"))
    )
    (net (code "101") (name "unconnected-(U2B-GPIO0_7_C18-PadC18)") (class "Default")
      (node (ref "U2") (pin "C18") (pinfunction "GPIO0_7_C18_C18") (pintype "bidirectional"))
    )
    (net (code "102") (name "unconnected-(U2B-GPIO0_19_A15-PadA15)") (class "Default")
      (node (ref "U2") (pin "A15") (pinfunction "GPIO0_19_A15_A15") (pintype "bidirectional"))
    )
    (net (code "103") (name "unconnected-(U2B-GPIO0_20_D14-PadD14)") (class "Default")
      (node (ref "U2") (pin "D14") (pinfunction "GPIO0_20_D14_D14") (pintype "bidirectional"))
    )
    (net (code "104") (name "unconnected-(U2B-GPIO0_26_T11-PadT11)") (class "Default")
      (node (ref "U2") (pin "T11") (pinfunction "GPIO0_26_T11_T11") (pintype "bidirectional"))
    )
    (net (code "105") (name "unconnected-(U2B-GPIO0_27_U12-PadU12)") (class "Default")
      (node (ref "U2") (pin "U12") (pinfunction "GPIO0_27_U12_U12") (pintype "bidirectional"))
    )
    (net (code "106") (name "unconnected-(U2B-GPIO1_12_T12-PadT12)") (class "Default")
      (node (ref "U2") (pin "T12") (pinfunction "GPIO1_12_T12_T12") (pintype "bidirectional"))
    )
    (net (code "107") (name "unconnected-(U2B-GPIO1_13_R12-PadR12)") (class "Default")
      (node (ref "U2") (pin "R12") (pinfunction "GPIO1_13_R12_R12") (pintype "bidirectional"))
    )
    (net (code "108") (name "unconnected-(U2B-GPIO1_14_V13-PadV13)") (class "Default")
      (node (ref "U2") (pin "V13") (pinfunction "GPIO1_14_V13_V13") (pintype "bidirectional"))
    )
    (net (code "109") (name "unconnected-(U2B-GPIO1_15_U13-PadU13)") (class "Default")
      (node (ref "U2") (pin "U13") (pinfunction "GPIO1_15_U13_U13") (pintype "bidirectional"))
    )
    (net (code "110") (name "unconnected-(U2B-GPIO1_16_R13-PadR13)") (class "Default")
      (node (ref "U2") (pin "R13") (pinfunction "GPIO1_16_R13_R13") (pintype "bidirectional"))
    )
    (net (code "111") (name "unconnected-(U2B-GPIO1_17_V14-PadV14)") (class "Default")
      (node (ref "U2") (pin "V14") (pinfunction "GPIO1_17_V14_V14") (pintype "bidirectional"))
    )
    (net (code "112") (name "unconnected-(U2B-GPIO1_28_U18-PadU18)") (class "Default")
      (node (ref "U2") (pin "U18") (pinfunction "GPIO1_28_U18_U18") (pintype "bidirectional"))
    )
    (net (code "113") (name "unconnected-(U2B-GPIO1_29_V6-PadV6)") (class "Default")
      (node (ref "U2") (pin "V6") (pinfunction "GPIO1_29_V6_V6") (pintype "bidirectional"))
    )
    (net (code "114") (name "unconnected-(U2B-GPIO2_0_T13-PadT13)") (class "Default")
      (node (ref "U2") (pin "T13") (pinfunction "GPIO2_0_T13_T13") (pintype "bidirectional"))
    )
    (net (code "115") (name "unconnected-(U2B-GPIO2_1_V12-PadV12)") (class "Default")
      (node (ref "U2") (pin "V12") (pinfunction "GPIO2_1_V12_V12") (pintype "bidirectional"))
    )
    (net (code "116") (name "unconnected-(U2B-GPIO3_18_B12-PadB12)") (class "Default")
      (node (ref "U2") (pin "B12") (pinfunction "GPIO3_18_B12_B12") (pintype "bidirectional"))
    )
    (net (code "117") (name "unconnected-(U2B-GPIO3_19_C13-PadC13)") (class "Default")
      (node (ref "U2") (pin "C13") (pinfunction "GPIO3_19_C13_C13") (pintype "bidirectional"))
    )
    (net (code "118") (name "unconnected-(U2B-GPIO3_20_D13-PadD13)") (class "Default")
      (node (ref "U2") (pin "D13") (pinfunction "GPIO3_20_D13_D13") (pintype "bidirectional"))
    )
    (net (code "119") (name "unconnected-(U2B-GPIO3_21_A14-PadA14)") (class "Default")
      (node (ref "U2") (pin "A14") (pinfunction "GPIO3_21_A14_A14") (pintype "bidirectional"))
    )
    (net (code "120") (name "unconnected-(U2B-I2C1_SCL_A16-PadA16)") (class "Default")
      (node (ref "U2") (pin "A16") (pinfunction "I2C1_SCL_A16_A16") (pintype "bidirectional"))
    )
    (net (code "121") (name "unconnected-(U2B-I2C1_SDA_B16-PadB16)") (class "Default")
      (node (ref "U2") (pin "B16") (pinfunction "I2C1_SDA_B16_B16") (pintype "bidirectional"))
    )
    (net (code "122") (name "unconnected-(U2B-I2C2_SCL_D17-PadD17)") (class "Default")
      (node (ref "U2") (pin "D17") (pinfunction "I2C2_SCL_D17_D17") (pintype "bidirectional"))
    )
    (net (code "123") (name "unconnected-(U2B-I2C2_SDA_D18-PadD18)") (class "Default")
      (node (ref "U2") (pin "D18") (pinfunction "I2C2_SDA_D18_D18") (pintype "bidirectional"))
    )
    (net (code "124") (name "unconnected-(U2B-JTAG_EMU0-PadC14)") (class "Default")
      (node (ref "U2") (pin "C14") (pinfunction "JTAG_EMU0_C14") (pintype "bidirectional"))
    )
    (net (code "125") (name "unconnected-(U2B-JTAG_EMU1-PadB14)") (class "Default")
      (node (ref "U2") (pin "B14") (pinfunction "JTAG_EMU1_B14") (pintype "bidirectional"))
    )
    (net (code "126") (name "unconnected-(U2B-JTAG_TCK-PadA12)") (class "Default")
      (node (ref "U2") (pin "A12") (pinfunction "JTAG_TCK_A12") (pintype "bidirectional"))
    )
    (net (code "127") (name "unconnected-(U2B-JTAG_TDI-PadB11)") (class "Default")
      (node (ref "U2") (pin "B11") (pinfunction "JTAG_TDI_B11") (pintype "bidirectional"))
    )
    (net (code "128") (name "unconnected-(U2B-JTAG_TDO-PadA11)") (class "Default")
      (node (ref "U2") (pin "A11") (pinfunction "JTAG_TDO_A11") (pintype "bidirectional"))
    )
    (net (code "129") (name "unconnected-(U2B-JTAG_TMS-PadC11)") (class "Default")
      (node (ref "U2") (pin "C11") (pinfunction "JTAG_TMS_C11") (pintype "bidirectional"))
    )
    (net (code "130") (name "unconnected-(U2B-MMC1_CLK_U9-PadU9)") (class "Default")
      (node (ref "U2") (pin "U9") (pinfunction "MMC1_CLK_U9_U9") (pintype "bidirectional"))
    )
    (net (code "131") (name "unconnected-(U2B-MMC1_CMD_V9-PadV9)") (class "Default")
      (node (ref "U2") (pin "V9") (pinfunction "MMC1_CMD_V9_V9") (pintype "bidirectional"))
    )
    (net (code "132") (name "unconnected-(U2B-MMC1_DAT0_U7-PadU7)") (class "Default")
      (node (ref "U2") (pin "U7") (pinfunction "MMC1_DAT0_U7_U7") (pintype "bidirectional"))
    )
    (net (code "133") (name "unconnected-(U2B-MMC1_DAT1_V7-PadV7)") (class "Default")
      (node (ref "U2") (pin "V7") (pinfunction "MMC1_DAT1_V7_V7") (pintype "bidirectional"))
    )
    (net (code "134") (name "unconnected-(U2B-MMC1_DAT2_R8-PadR8)") (class "Default")
      (node (ref "U2") (pin "R8") (pinfunction "MMC1_DAT2_R8_R8") (pintype "bidirectional"))
    )
    (net (code "135") (name "unconnected-(U2B-MMC1_DAT3_T8-PadT8)") (class "Default")
      (node (ref "U2") (pin "T8") (pinfunction "MMC1_DAT3_T8_T8") (pintype "bidirectional"))
    )
    (net (code "136") (name "unconnected-(U2B-MMC1_DAT4_U8-PadU8)") (class "Default")
      (node (ref "U2") (pin "U8") (pinfunction "MMC1_DAT4_U8_U8") (pintype "bidirectional"))
    )
    (net (code "137") (name "unconnected-(U2B-MMC1_DAT5_V8-PadV8)") (class "Default")
      (node (ref "U2") (pin "V8") (pinfunction "MMC1_DAT5_V8_V8") (pintype "bidirectional"))
    )
    (net (code "138") (name "unconnected-(U2B-MMC1_DAT6_R9-PadR9)") (class "Default")
      (node (ref "U2") (pin "R9") (pinfunction "MMC1_DAT6_R9_R9") (pintype "bidirectional"))
    )
    (net (code "139") (name "unconnected-(U2B-MMC1_DAT7_T9-PadT9)") (class "Default")
      (node (ref "U2") (pin "T9") (pinfunction "MMC1_DAT7_T9_T9") (pintype "bidirectional"))
    )
    (net (code "140") (name "unconnected-(U2B-SPI1_CLK_A13-PadA13)") (class "Default")
      (node (ref "U2") (pin "A13") (pinfunction "SPI1_CLK_A13_A13") (pintype "bidirectional"))
    )
    (net (code "141") (name "unconnected-(U2B-SPI1_CS0_C12-PadC12)") (class "Default")
      (node (ref "U2") (pin "C12") (pinfunction "SPI1_CS0_C12_C12") (pintype "bidirectional"))
    )
    (net (code "142") (name "unconnected-(U2B-SPI1_D0_B13-PadB13)") (class "Default")
      (node (ref "U2") (pin "B13") (pinfunction "SPI1_D0_B13_B13") (pintype "bidirectional"))
    )
    (net (code "143") (name "unconnected-(U2B-SPI1_D1_D12-PadD12)") (class "Default")
      (node (ref "U2") (pin "D12") (pinfunction "SPI1_D1_D12_D12") (pintype "bidirectional"))
    )
    (net (code "144") (name "unconnected-(U2B-TIMER4_R7-PadR7)") (class "Default")
      (node (ref "U2") (pin "R7") (pinfunction "TIMER4_R7_R7") (pintype "bidirectional"))
    )
    (net (code "145") (name "unconnected-(U2B-TIMER5_T6-PadT6)") (class "Default")
      (node (ref "U2") (pin "T6") (pinfunction "TIMER5_T6_T6") (pintype "bidirectional"))
    )
    (net (code "146") (name "unconnected-(U2B-TIMER6_U6-PadU6)") (class "Default")
      (node (ref "U2") (pin "U6") (pinfunction "TIMER6_U6_U6") (pintype "bidirectional"))
    )
    (net (code "147") (name "unconnected-(U2B-TIMER7_T7-PadT7)") (class "Default")
      (node (ref "U2") (pin "T7") (pinfunction "TIMER7_T7_T7") (pintype "bidirectional"))
    )
    (net (code "148") (name "unconnected-(U2B-UART0_CTSN_E18-PadE18)") (class "Default")
      (node (ref "U2") (pin "E18") (pinfunction "UART0_CTSN_E18_E18") (pintype "bidirectional"))
    )
    (net (code "149") (name "unconnected-(U2B-UART0_RTSN_E17-PadE17)") (class "Default")
      (node (ref "U2") (pin "E17") (pinfunction "UART0_RTSN_E17_E17") (pintype "bidirectional"))
    )
    (net (code "150") (name "unconnected-(U2B-UART0_RXD_E15-PadE15)") (class "Default")
      (node (ref "U2") (pin "E15") (pinfunction "UART0_RXD_E15_E15") (pintype "bidirectional"))
    )
    (net (code "151") (name "unconnected-(U2B-UART0_TXD_E16-PadE16)") (class "Default")
      (node (ref "U2") (pin "E16") (pinfunction "UART0_TXD_E16_E16") (pintype "bidirectional"))
    )
    (net (code "152") (name "unconnected-(U2B-UART1_RXD_D16-PadD16)") (class "Default")
      (node (ref "U2") (pin "D16") (pinfunction "UART1_RXD_D16_D16") (pintype "bidirectional"))
    )
    (net (code "153") (name "unconnected-(U2B-UART1_TXD_D15-PadD15)") (class "Default")
      (node (ref "U2") (pin "D15") (pinfunction "UART1_TXD_D15_D15") (pintype "bidirectional"))
    )
    (net (code "154") (name "unconnected-(U2B-UART2_RXD_A17-PadA17)") (class "Default")
      (node (ref "U2") (pin "A17") (pinfunction "UART2_RXD_A17_A17") (pintype "bidirectional"))
    )
    (net (code "155") (name "unconnected-(U2B-UART2_TXD_B17-PadB17)") (class "Default")
      (node (ref "U2") (pin "B17") (pinfunction "UART2_TXD_B17_B17") (pintype "bidirectional"))
    )
    (net (code "156") (name "unconnected-(U2B-UART4_RXD_T17-PadT17)") (class "Default")
      (node (ref "U2") (pin "T17") (pinfunction "UART4_RXD_T17_T17") (pintype "bidirectional"))
    )
    (net (code "157") (name "unconnected-(U2B-UART4_TXD_U17-PadU17)") (class "Default")
      (node (ref "U2") (pin "U17") (pinfunction "UART4_TXD_U17_U17") (pintype "bidirectional"))
    )
    (net (code "158") (name "unconnected-(U2C-ADC_VREFP-PadB9)") (class "Default")
      (node (ref "U2") (pin "B9") (pinfunction "ADC_VREFP_B9") (pintype "bidirectional"))
    )
    (net (code "159") (name "unconnected-(U2C-AIN0-PadB6)") (class "Default")
      (node (ref "U2") (pin "B6") (pinfunction "AIN0_B6") (pintype "bidirectional"))
    )
    (net (code "160") (name "unconnected-(U2C-AIN1-PadC7)") (class "Default")
      (node (ref "U2") (pin "C7") (pinfunction "AIN1_C7") (pintype "bidirectional"))
    )
    (net (code "161") (name "unconnected-(U2C-AIN2-PadB7)") (class "Default")
      (node (ref "U2") (pin "B7") (pinfunction "AIN2_B7") (pintype "bidirectional"))
    )
    (net (code "162") (name "unconnected-(U2C-AIN3-PadA7)") (class "Default")
      (node (ref "U2") (pin "A7") (pinfunction "AIN3_A7") (pintype "bidirectional"))
    )
    (net (code "163") (name "unconnected-(U2C-AIN4-PadC8)") (class "Default")
      (node (ref "U2") (pin "C8") (pinfunction "AIN4_C8") (pintype "bidirectional"))
    )
    (net (code "164") (name "unconnected-(U2C-AIN5-PadB8)") (class "Default")
      (node (ref "U2") (pin "B8") (pinfunction "AIN5_B8") (pintype "bidirectional"))
    )
    (net (code "165") (name "unconnected-(U2C-AIN6-PadA8)") (class "Default")
      (node (ref "U2") (pin "A8") (pinfunction "AIN6_A8") (pintype "bidirectional"))
    )
    (net (code "166") (name "unconnected-(U2C-AIN7-PadC9)") (class "Default")
      (node (ref "U2") (pin "C9") (pinfunction "AIN7_C9") (pintype "bidirectional"))
    )
    (net (code "167") (name "unconnected-(U2C-HDMIDIS_GPIO1_27_V17-PadV17)") (class "Default")
      (node (ref "U2") (pin "V17") (pinfunction "HDMIDIS_GPIO1_27_V17_V17") (pintype "bidirectional"))
    )
    (net (code "168") (name "unconnected-(U2C-HDMIINT_GPIO1_25_U16-PadU16)") (class "Default")
      (node (ref "U2") (pin "U16") (pinfunction "HDMIINT_GPIO1_25_U16_U16") (pintype "bidirectional"))
    )
    (net (code "169") (name "unconnected-(U2C-LCD_DE_R6-PadR6)") (class "Default")
      (node (ref "U2") (pin "R6") (pinfunction "LCD_DE_R6_R6") (pintype "bidirectional"))
    )
    (net (code "170") (name "unconnected-(U2C-LCD_HSYNC_R5-PadR5)") (class "Default")
      (node (ref "U2") (pin "R5") (pinfunction "LCD_HSYNC_R5_R5") (pintype "bidirectional"))
    )
    (net (code "171") (name "unconnected-(U2C-LCD_PCLK_V5-PadV5)") (class "Default")
      (node (ref "U2") (pin "V5") (pinfunction "LCD_PCLK_V5_V5") (pintype "bidirectional"))
    )
    (net (code "172") (name "unconnected-(U2C-LCD_VSYNC_U5-PadU5)") (class "Default")
      (node (ref "U2") (pin "U5") (pinfunction "LCD_VSYNC_U5_U5") (pintype "bidirectional"))
    )
    (net (code "173") (name "unconnected-(U2C-USB0_CE-PadM15)") (class "Default")
      (node (ref "U2") (pin "M15") (pinfunction "USB0_CE_M15") (pintype "bidirectional"))
    )
    (net (code "174") (name "unconnected-(U2C-USB0_DRVVBUS-PadF16)") (class "Default")
      (node (ref "U2") (pin "F16") (pinfunction "USB0_DRVVBUS_F16") (pintype "bidirectional"))
    )
    (net (code "175") (name "unconnected-(U2C-USB1OC_GPIO1_26_T16-PadT16)") (class "Default")
      (node (ref "U2") (pin "T16") (pinfunction "USB1OC_GPIO1_26_T16_T16") (pintype "bidirectional"))
    )
    (net (code "176") (name "unconnected-(U2C-USB1_CE-PadP18)") (class "Default")
      (node (ref "U2") (pin "P18") (pinfunction "USB1_CE_P18") (pintype "bidirectional"))
    )
    (net (code "177") (name "unconnected-(U2C-USB1_DRVVBUS-PadF15)") (class "Default")
      (node (ref "U2") (pin "F15") (pinfunction "USB1_DRVVBUS_F15") (pintype "bidirectional"))
    )
    (net (code "178") (name "unconnected-(U2C-VOUT_ADC_1P8V_0-PadA4)") (class "Default")
      (node (ref "U2") (pin "A4") (pinfunction "VOUT_ADC_1P8V_0_A4") (pintype "bidirectional"))
    )
    (net (code "179") (name "unconnected-(U2C-VOUT_ADC_1P8V_1-PadA5)") (class "Default")
      (node (ref "U2") (pin "A5") (pinfunction "VOUT_ADC_1P8V_1_A5") (pintype "bidirectional"))
    )
    (net (code "180") (name "unconnected-(U2C-VSSA_ADC_0-PadA6)") (class "Default")
      (node (ref "U2") (pin "A6") (pinfunction "VSSA_ADC_0_A6") (pintype "bidirectional"))
    )
    (net (code "181") (name "unconnected-(U2C-VSSA_ADC_1-PadA9)") (class "Default")
      (node (ref "U2") (pin "A9") (pinfunction "VSSA_ADC_1_A9") (pintype "bidirectional"))
    )
    (net (code "182") (name "unconnected-(U2C-VSSA_ADC_2-PadE8)") (class "Default")
      (node (ref "U2") (pin "E8") (pinfunction "VSSA_ADC_2_E8") (pintype "bidirectional"))
    )
    (net (code "183") (name "unconnected-(U2E-CAP_VBB_MPU-PadC10)") (class "Default")
      (node (ref "U2") (pin "C10") (pinfunction "CAP_VBB_MPU_C10") (pintype "bidirectional"))
    )
    (net (code "184") (name "unconnected-(U2E-CAP_VDD_RTC-PadD6)") (class "Default")
      (node (ref "U2") (pin "D6") (pinfunction "CAP_VDD_RTC_D6") (pintype "bidirectional"))
    )
    (net (code "185") (name "unconnected-(U2E-CAP_VDD_SRAM_COR-PadD9)") (class "Default")
      (node (ref "U2") (pin "D9") (pinfunction "CAP_VDD_SRAM_COR_D9") (pintype "bidirectional"))
    )
    (net (code "186") (name "unconnected-(U2E-CAP_VDD_SRAM_MPU-PadD11)") (class "Default")
      (node (ref "U2") (pin "D11") (pinfunction "CAP_VDD_SRAM_MPU_D11") (pintype "bidirectional"))
    )
    (net (code "187") (name "unconnected-(U2E-TESTOUT-PadA3)") (class "Default")
      (node (ref "U2") (pin "A3") (pinfunction "TESTOUT_A3") (pintype "bidirectional"))
    )
    (net (code "188") (name "unconnected-(U2E-VDDA_ADC-PadD8)") (class "Default")
      (node (ref "U2") (pin "D8") (pinfunction "VDDA_ADC_D8") (pintype "bidirectional"))
    )
    (net (code "189") (name "unconnected-(U2E-VDDS_DDR1-PadE5)") (class "Default")
      (node (ref "U2") (pin "E5") (pinfunction "VDDS_DDR1_E5") (pintype "bidirectional"))
    )
    (net (code "190") (name "unconnected-(U2E-VDDS_DDR2-PadF5)") (class "Default")
      (node (ref "U2") (pin "F5") (pinfunction "VDDS_DDR2_F5") (pintype "bidirectional"))
    )
    (net (code "191") (name "unconnected-(U2E-VDDS_DDR3-PadG5)") (class "Default")
      (node (ref "U2") (pin "G5") (pinfunction "VDDS_DDR3_G5") (pintype "bidirectional"))
    )
    (net (code "192") (name "unconnected-(U2E-VDDS_DDR4-PadH5)") (class "Default")
      (node (ref "U2") (pin "H5") (pinfunction "VDDS_DDR4_H5") (pintype "bidirectional"))
    )
    (net (code "193") (name "unconnected-(U2E-VDDS_DDR5-PadJ5)") (class "Default")
      (node (ref "U2") (pin "J5") (pinfunction "VDDS_DDR5_J5") (pintype "bidirectional"))
    )
    (net (code "194") (name "unconnected-(U2E-VDDS_DDR6-PadK5)") (class "Default")
      (node (ref "U2") (pin "K5") (pinfunction "VDDS_DDR6_K5") (pintype "bidirectional"))
    )
    (net (code "195") (name "unconnected-(U2E-VDDS_DDR7-PadL5)") (class "Default")
      (node (ref "U2") (pin "L5") (pinfunction "VDDS_DDR7_L5") (pintype "bidirectional"))
    )
    (net (code "196") (name "unconnected-(U2E-VDD_3V3A1-PadE10)") (class "Default")
      (node (ref "U2") (pin "E10") (pinfunction "VDD_3V3A1_E10") (pintype "bidirectional"))
    )
    (net (code "197") (name "unconnected-(U2E-VDD_3V3A2-PadE11)") (class "Default")
      (node (ref "U2") (pin "E11") (pinfunction "VDD_3V3A2_E11") (pintype "bidirectional"))
    )
    (net (code "198") (name "unconnected-(U2E-VDD_3V3A3-PadE12)") (class "Default")
      (node (ref "U2") (pin "E12") (pinfunction "VDD_3V3A3_E12") (pintype "bidirectional"))
    )
    (net (code "199") (name "unconnected-(U2E-VDD_3V3A4-PadE13)") (class "Default")
      (node (ref "U2") (pin "E13") (pinfunction "VDD_3V3A4_E13") (pintype "bidirectional"))
    )
    (net (code "200") (name "unconnected-(U2E-VDD_3V3A5-PadF14)") (class "Default")
      (node (ref "U2") (pin "F14") (pinfunction "VDD_3V3A5_F14") (pintype "bidirectional"))
    )
    (net (code "201") (name "unconnected-(U2E-VDD_3V3A6-PadG14)") (class "Default")
      (node (ref "U2") (pin "G14") (pinfunction "VDD_3V3A6_G14") (pintype "bidirectional"))
    )
    (net (code "202") (name "unconnected-(U2E-VDD_3V3A7-PadH14)") (class "Default")
      (node (ref "U2") (pin "H14") (pinfunction "VDD_3V3A7_H14") (pintype "bidirectional"))
    )
    (net (code "203") (name "unconnected-(U2E-VDD_3V3A8-PadJ14)") (class "Default")
      (node (ref "U2") (pin "J14") (pinfunction "VDD_3V3A8_J14") (pintype "bidirectional"))
    )
    (net (code "204") (name "unconnected-(U2E-VDD_3V3A9-PadK14)") (class "Default")
      (node (ref "U2") (pin "K14") (pinfunction "VDD_3V3A9_K14") (pintype "bidirectional"))
    )
    (net (code "205") (name "unconnected-(U2E-VDD_3V3A10-PadL14)") (class "Default")
      (node (ref "U2") (pin "L14") (pinfunction "VDD_3V3A10_L14") (pintype "bidirectional"))
    )
    (net (code "206") (name "unconnected-(U2E-VDD_3V3A11-PadN5)") (class "Default")
      (node (ref "U2") (pin "N5") (pinfunction "VDD_3V3A11_N5") (pintype "bidirectional"))
    )
    (net (code "207") (name "unconnected-(U2E-VDD_3V3A12-PadN15)") (class "Default")
      (node (ref "U2") (pin "N15") (pinfunction "VDD_3V3A12_N15") (pintype "bidirectional"))
    )
    (net (code "208") (name "unconnected-(U2E-VDD_3V3A13-PadP5)") (class "Default")
      (node (ref "U2") (pin "P5") (pinfunction "VDD_3V3A13_P5") (pintype "bidirectional"))
    )
    (net (code "209") (name "unconnected-(U2E-VDD_3V3A14-PadP6)") (class "Default")
      (node (ref "U2") (pin "P6") (pinfunction "VDD_3V3A14_P6") (pintype "bidirectional"))
    )
    (net (code "210") (name "unconnected-(U2E-VDD_3V3A15-PadP7)") (class "Default")
      (node (ref "U2") (pin "P7") (pinfunction "VDD_3V3A15_P7") (pintype "bidirectional"))
    )
    (net (code "211") (name "unconnected-(U2E-VDD_3V3A16-PadP8)") (class "Default")
      (node (ref "U2") (pin "P8") (pinfunction "VDD_3V3A16_P8") (pintype "bidirectional"))
    )
    (net (code "212") (name "unconnected-(U2E-VDD_3V3A17-PadP10)") (class "Default")
      (node (ref "U2") (pin "P10") (pinfunction "VDD_3V3A17_P10") (pintype "bidirectional"))
    )
    (net (code "213") (name "unconnected-(U2E-VDD_3V3A18-PadP11)") (class "Default")
      (node (ref "U2") (pin "P11") (pinfunction "VDD_3V3A18_P11") (pintype "bidirectional"))
    )
    (net (code "214") (name "unconnected-(U2E-VDD_3V3A19-PadP12)") (class "Default")
      (node (ref "U2") (pin "P12") (pinfunction "VDD_3V3A19_P12") (pintype "bidirectional"))
    )
    (net (code "215") (name "unconnected-(U2E-VDD_3V3A20-PadP13)") (class "Default")
      (node (ref "U2") (pin "P13") (pinfunction "VDD_3V3A20_P13") (pintype "bidirectional"))
    )
    (net (code "216") (name "unconnected-(U2E-VDD_3V3A21-PadR15)") (class "Default")
      (node (ref "U2") (pin "R15") (pinfunction "VDD_3V3A21_R15") (pintype "bidirectional"))
    )
    (net (code "217") (name "unconnected-(U2E-VDD_CORE1-PadF6)") (class "Default")
      (node (ref "U2") (pin "F6") (pinfunction "VDD_CORE1_F6") (pintype "bidirectional"))
    )
    (net (code "218") (name "unconnected-(U2E-VDD_CORE2-PadF7)") (class "Default")
      (node (ref "U2") (pin "F7") (pinfunction "VDD_CORE2_F7") (pintype "bidirectional"))
    )
    (net (code "219") (name "unconnected-(U2E-VDD_CORE3-PadG6)") (class "Default")
      (node (ref "U2") (pin "G6") (pinfunction "VDD_CORE3_G6") (pintype "bidirectional"))
    )
    (net (code "220") (name "unconnected-(U2E-VDD_CORE4-PadG7)") (class "Default")
      (node (ref "U2") (pin "G7") (pinfunction "VDD_CORE4_G7") (pintype "bidirectional"))
    )
    (net (code "221") (name "unconnected-(U2E-VDD_CORE5-PadG10)") (class "Default")
      (node (ref "U2") (pin "G10") (pinfunction "VDD_CORE5_G10") (pintype "bidirectional"))
    )
    (net (code "222") (name "unconnected-(U2E-VDD_CORE6-PadH11)") (class "Default")
      (node (ref "U2") (pin "H11") (pinfunction "VDD_CORE6_H11") (pintype "bidirectional"))
    )
    (net (code "223") (name "unconnected-(U2E-VDD_CORE7-PadJ12)") (class "Default")
      (node (ref "U2") (pin "J12") (pinfunction "VDD_CORE7_J12") (pintype "bidirectional"))
    )
    (net (code "224") (name "unconnected-(U2E-VDD_CORE8-PadK6)") (class "Default")
      (node (ref "U2") (pin "K6") (pinfunction "VDD_CORE8_K6") (pintype "bidirectional"))
    )
    (net (code "225") (name "unconnected-(U2E-VDD_CORE9-PadK8)") (class "Default")
      (node (ref "U2") (pin "K8") (pinfunction "VDD_CORE9_K8") (pintype "bidirectional"))
    )
    (net (code "226") (name "unconnected-(U2E-VDD_CORE10-PadK12)") (class "Default")
      (node (ref "U2") (pin "K12") (pinfunction "VDD_CORE10_K12") (pintype "bidirectional"))
    )
    (net (code "227") (name "unconnected-(U2E-VDD_CORE11-PadL6)") (class "Default")
      (node (ref "U2") (pin "L6") (pinfunction "VDD_CORE11_L6") (pintype "bidirectional"))
    )
    (net (code "228") (name "unconnected-(U2E-VDD_CORE12-PadL7)") (class "Default")
      (node (ref "U2") (pin "L7") (pinfunction "VDD_CORE12_L7") (pintype "bidirectional"))
    )
    (net (code "229") (name "unconnected-(U2E-VDD_CORE13-PadL8)") (class "Default")
      (node (ref "U2") (pin "L8") (pinfunction "VDD_CORE13_L8") (pintype "bidirectional"))
    )
    (net (code "230") (name "unconnected-(U2E-VDD_CORE14-PadL9)") (class "Default")
      (node (ref "U2") (pin "L9") (pinfunction "VDD_CORE14_L9") (pintype "bidirectional"))
    )
    (net (code "231") (name "unconnected-(U2E-VDD_CORE15-PadM11)") (class "Default")
      (node (ref "U2") (pin "M11") (pinfunction "VDD_CORE15_M11") (pintype "bidirectional"))
    )
    (net (code "232") (name "unconnected-(U2E-VDD_CORE16-PadM13)") (class "Default")
      (node (ref "U2") (pin "M13") (pinfunction "VDD_CORE16_M13") (pintype "bidirectional"))
    )
    (net (code "233") (name "unconnected-(U2E-VDD_CORE17-PadN8)") (class "Default")
      (node (ref "U2") (pin "N8") (pinfunction "VDD_CORE17_N8") (pintype "bidirectional"))
    )
    (net (code "234") (name "unconnected-(U2E-VDD_CORE18-PadN9)") (class "Default")
      (node (ref "U2") (pin "N9") (pinfunction "VDD_CORE18_N9") (pintype "bidirectional"))
    )
    (net (code "235") (name "unconnected-(U2E-VDD_CORE19-PadN12)") (class "Default")
      (node (ref "U2") (pin "N12") (pinfunction "VDD_CORE19_N12") (pintype "bidirectional"))
    )
    (net (code "236") (name "unconnected-(U2E-VDD_CORE20-PadN13)") (class "Default")
      (node (ref "U2") (pin "N13") (pinfunction "VDD_CORE20_N13") (pintype "bidirectional"))
    )
    (net (code "237") (name "unconnected-(U2E-VDD_MPU0-PadF10)") (class "Default")
      (node (ref "U2") (pin "F10") (pinfunction "VDD_MPU0_F10") (pintype "bidirectional"))
    )
    (net (code "238") (name "unconnected-(U2E-VDD_MPU1-PadF11)") (class "Default")
      (node (ref "U2") (pin "F11") (pinfunction "VDD_MPU1_F11") (pintype "bidirectional"))
    )
    (net (code "239") (name "unconnected-(U2E-VDD_MPU2-PadF12)") (class "Default")
      (node (ref "U2") (pin "F12") (pinfunction "VDD_MPU2_F12") (pintype "bidirectional"))
    )
    (net (code "240") (name "unconnected-(U2E-VDD_MPU3-PadF13)") (class "Default")
      (node (ref "U2") (pin "F13") (pinfunction "VDD_MPU3_F13") (pintype "bidirectional"))
    )
    (net (code "241") (name "unconnected-(U2E-VDD_MPU4-PadG13)") (class "Default")
      (node (ref "U2") (pin "G13") (pinfunction "VDD_MPU4_G13") (pintype "bidirectional"))
    )
    (net (code "242") (name "unconnected-(U2E-VDD_MPU5-PadH13)") (class "Default")
      (node (ref "U2") (pin "H13") (pinfunction "VDD_MPU5_H13") (pintype "bidirectional"))
    )
    (net (code "243") (name "unconnected-(U2E-VDD_MPU6-PadJ13)") (class "Default")
      (node (ref "U2") (pin "J13") (pinfunction "VDD_MPU6_J13") (pintype "bidirectional"))
    )
    (net (code "244") (name "unconnected-(U2E-VDD_MPU_MON-PadA2)") (class "Default")
      (node (ref "U2") (pin "A2") (pinfunction "VDD_MPU_MON_A2") (pintype "bidirectional"))
    )
    (net (code "245") (name "unconnected-(U2E-VDD_PLL1-PadE7)") (class "Default")
      (node (ref "U2") (pin "E7") (pinfunction "VDD_PLL1_E7") (pintype "bidirectional"))
    )
    (net (code "246") (name "unconnected-(U2E-VDD_PLL2-PadH15)") (class "Default")
      (node (ref "U2") (pin "H15") (pinfunction "VDD_PLL2_H15") (pintype "bidirectional"))
    )
    (net (code "247") (name "unconnected-(U2E-VDD_PLL3-PadR10)") (class "Default")
      (node (ref "U2") (pin "R10") (pinfunction "VDD_PLL3_R10") (pintype "bidirectional"))
    )
    (net (code "248") (name "unconnected-(U2E-VDD_PLL4-PadR11)") (class "Default")
      (node (ref "U2") (pin "R11") (pinfunction "VDD_PLL4_R11") (pintype "bidirectional"))
    )
    (net (code "249") (name "unconnected-(U2E-VDD_RTC1-PadD7)") (class "Default")
      (node (ref "U2") (pin "D7") (pinfunction "VDD_RTC1_D7") (pintype "bidirectional"))
    )
    (net (code "250") (name "unconnected-(U2E-VDD_RTC2-PadE6)") (class "Default")
      (node (ref "U2") (pin "E6") (pinfunction "VDD_RTC2_E6") (pintype "bidirectional"))
    )
    (net (code "251") (name "unconnected-(U2E-VDD_RTC4-PadF9)") (class "Default")
      (node (ref "U2") (pin "F9") (pinfunction "VDD_RTC4_F9") (pintype "bidirectional"))
    )
    (net (code "252") (name "unconnected-(U2E-VDD_RTC5-PadK13)") (class "Default")
      (node (ref "U2") (pin "K13") (pinfunction "VDD_RTC5_K13") (pintype "bidirectional"))
    )
    (net (code "253") (name "unconnected-(U2E-VDD_RTC6-PadN6)") (class "Default")
      (node (ref "U2") (pin "N6") (pinfunction "VDD_RTC6_N6") (pintype "bidirectional"))
    )
    (net (code "254") (name "unconnected-(U2E-VDD_RTC7-PadP9)") (class "Default")
      (node (ref "U2") (pin "P9") (pinfunction "VDD_RTC7_P9") (pintype "bidirectional"))
    )
    (net (code "255") (name "unconnected-(U2E-VDD_RTC8-PadP14)") (class "Default")
      (node (ref "U2") (pin "P14") (pinfunction "VDD_RTC8_P14") (pintype "bidirectional"))
    )
    (net (code "256") (name "unconnected-(U2E-VPP-PadM5)") (class "Default")
      (node (ref "U2") (pin "M5") (pinfunction "VPP_M5") (pintype "bidirectional"))
    )
    (net (code "257") (name "unconnected-(U2F-DGND2-PadA18)") (class "Default")
      (node (ref "U2") (pin "A18") (pinfunction "DGND2_A18") (pintype "bidirectional"))
    )
    (net (code "258") (name "unconnected-(U2F-DGND3-PadE19)") (class "Default")
      (node (ref "U2") (pin "E19") (pinfunction "DGND3_E19") (pintype "bidirectional"))
    )
    (net (code "259") (name "unconnected-(U2F-DGND4-PadE20)") (class "Default")
      (node (ref "U2") (pin "E20") (pinfunction "DGND4_E20") (pintype "bidirectional"))
    )
    (net (code "260") (name "unconnected-(U2F-DGND5-PadF8)") (class "Default")
      (node (ref "U2") (pin "F8") (pinfunction "DGND5_F8") (pintype "bidirectional"))
    )
    (net (code "261") (name "unconnected-(U2F-DGND6-PadF19)") (class "Default")
      (node (ref "U2") (pin "F19") (pinfunction "DGND6_F19") (pintype "bidirectional"))
    )
    (net (code "262") (name "unconnected-(U2F-DGND7-PadG8)") (class "Default")
      (node (ref "U2") (pin "G8") (pinfunction "DGND7_G8") (pintype "bidirectional"))
    )
    (net (code "263") (name "unconnected-(U2F-DGND8-PadG9)") (class "Default")
      (node (ref "U2") (pin "G9") (pinfunction "DGND8_G9") (pintype "bidirectional"))
    )
    (net (code "264") (name "unconnected-(U2F-DGND9-PadG11)") (class "Default")
      (node (ref "U2") (pin "G11") (pinfunction "DGND9_G11") (pintype "bidirectional"))
    )
    (net (code "265") (name "unconnected-(U2F-DGND10-PadG12)") (class "Default")
      (node (ref "U2") (pin "G12") (pinfunction "DGND10_G12") (pintype "bidirectional"))
    )
    (net (code "266") (name "unconnected-(U2F-DGND11-PadG19)") (class "Default")
      (node (ref "U2") (pin "G19") (pinfunction "DGND11_G19") (pintype "bidirectional"))
    )
    (net (code "267") (name "unconnected-(U2F-DGND12-PadH6)") (class "Default")
      (node (ref "U2") (pin "H6") (pinfunction "DGND12_H6") (pintype "bidirectional"))
    )
    (net (code "268") (name "unconnected-(U2F-DGND13-PadH7)") (class "Default")
      (node (ref "U2") (pin "H7") (pinfunction "DGND13_H7") (pintype "bidirectional"))
    )
    (net (code "269") (name "unconnected-(U2F-DGND14-PadH8)") (class "Default")
      (node (ref "U2") (pin "H8") (pinfunction "DGND14_H8") (pintype "bidirectional"))
    )
    (net (code "270") (name "unconnected-(U2F-DGND15-PadH9)") (class "Default")
      (node (ref "U2") (pin "H9") (pinfunction "DGND15_H9") (pintype "bidirectional"))
    )
    (net (code "271") (name "unconnected-(U2F-DGND16-PadH10)") (class "Default")
      (node (ref "U2") (pin "H10") (pinfunction "DGND16_H10") (pintype "bidirectional"))
    )
    (net (code "272") (name "unconnected-(U2F-DGND17-PadH12)") (class "Default")
      (node (ref "U2") (pin "H12") (pinfunction "DGND17_H12") (pintype "bidirectional"))
    )
    (net (code "273") (name "unconnected-(U2F-DGND18-PadH19)") (class "Default")
      (node (ref "U2") (pin "H19") (pinfunction "DGND18_H19") (pintype "bidirectional"))
    )
    (net (code "274") (name "unconnected-(U2F-DGND20-PadJ7)") (class "Default")
      (node (ref "U2") (pin "J7") (pinfunction "DGND20_J7") (pintype "bidirectional"))
    )
    (net (code "275") (name "unconnected-(U2F-DGND21-PadJ8)") (class "Default")
      (node (ref "U2") (pin "J8") (pinfunction "DGND21_J8") (pintype "bidirectional"))
    )
    (net (code "276") (name "unconnected-(U2F-DGND22-PadJ9)") (class "Default")
      (node (ref "U2") (pin "J9") (pinfunction "DGND22_J9") (pintype "bidirectional"))
    )
    (net (code "277") (name "unconnected-(U2F-DGND23-PadJ10)") (class "Default")
      (node (ref "U2") (pin "J10") (pinfunction "DGND23_J10") (pintype "bidirectional"))
    )
    (net (code "278") (name "unconnected-(U2F-DGND24-PadJ11)") (class "Default")
      (node (ref "U2") (pin "J11") (pinfunction "DGND24_J11") (pintype "bidirectional"))
    )
    (net (code "279") (name "unconnected-(U2F-DGND25-PadJ19)") (class "Default")
      (node (ref "U2") (pin "J19") (pinfunction "DGND25_J19") (pintype "bidirectional"))
    )
    (net (code "280") (name "unconnected-(U2F-DGND26-PadJ20)") (class "Default")
      (node (ref "U2") (pin "J20") (pinfunction "DGND26_J20") (pintype "bidirectional"))
    )
    (net (code "281") (name "unconnected-(U2F-DGND27-PadK7)") (class "Default")
      (node (ref "U2") (pin "K7") (pinfunction "DGND27_K7") (pintype "bidirectional"))
    )
    (net (code "282") (name "unconnected-(U2F-DGND28-PadK9)") (class "Default")
      (node (ref "U2") (pin "K9") (pinfunction "DGND28_K9") (pintype "bidirectional"))
    )
    (net (code "283") (name "unconnected-(U2F-DGND29-PadK10)") (class "Default")
      (node (ref "U2") (pin "K10") (pinfunction "DGND29_K10") (pintype "bidirectional"))
    )
    (net (code "284") (name "unconnected-(U2F-DGND30-PadK11)") (class "Default")
      (node (ref "U2") (pin "K11") (pinfunction "DGND30_K11") (pintype "bidirectional"))
    )
    (net (code "285") (name "unconnected-(U2F-DGND31-PadK19)") (class "Default")
      (node (ref "U2") (pin "K19") (pinfunction "DGND31_K19") (pintype "bidirectional"))
    )
    (net (code "286") (name "unconnected-(U2F-DGND32-PadL10)") (class "Default")
      (node (ref "U2") (pin "L10") (pinfunction "DGND32_L10") (pintype "bidirectional"))
    )
    (net (code "287") (name "unconnected-(U2F-DGND33-PadL11)") (class "Default")
      (node (ref "U2") (pin "L11") (pinfunction "DGND33_L11") (pintype "bidirectional"))
    )
    (net (code "288") (name "unconnected-(U2F-DGND34-PadL12)") (class "Default")
      (node (ref "U2") (pin "L12") (pinfunction "DGND34_L12") (pintype "bidirectional"))
    )
    (net (code "289") (name "unconnected-(U2F-DGND35-PadL13)") (class "Default")
      (node (ref "U2") (pin "L13") (pinfunction "DGND35_L13") (pintype "bidirectional"))
    )
    (net (code "290") (name "unconnected-(U2F-DGND38-PadM6)") (class "Default")
      (node (ref "U2") (pin "M6") (pinfunction "DGND38_M6") (pintype "bidirectional"))
    )
    (net (code "291") (name "unconnected-(U2F-DGND39-PadM7)") (class "Default")
      (node (ref "U2") (pin "M7") (pinfunction "DGND39_M7") (pintype "bidirectional"))
    )
    (net (code "292") (name "unconnected-(U2F-DGND40-PadM8)") (class "Default")
      (node (ref "U2") (pin "M8") (pinfunction "DGND40_M8") (pintype "bidirectional"))
    )
    (net (code "293") (name "unconnected-(U2F-DGND41-PadM9)") (class "Default")
      (node (ref "U2") (pin "M9") (pinfunction "DGND41_M9") (pintype "bidirectional"))
    )
    (net (code "294") (name "unconnected-(U2F-DGND43-PadM12)") (class "Default")
      (node (ref "U2") (pin "M12") (pinfunction "DGND43_M12") (pintype "bidirectional"))
    )
    (net (code "295") (name "unconnected-(U2F-DGND44-PadM14)") (class "Default")
      (node (ref "U2") (pin "M14") (pinfunction "DGND44_M14") (pintype "bidirectional"))
    )
    (net (code "296") (name "unconnected-(U2F-DGND47-PadN10)") (class "Default")
      (node (ref "U2") (pin "N10") (pinfunction "DGND47_N10") (pintype "bidirectional"))
    )
    (net (code "297") (name "unconnected-(U2F-DGND48-PadN11)") (class "Default")
      (node (ref "U2") (pin "N11") (pinfunction "DGND48_N11") (pintype "bidirectional"))
    )
    (net (code "298") (name "unconnected-(U2F-DGND49-PadN14)") (class "Default")
      (node (ref "U2") (pin "N14") (pinfunction "DGND49_N14") (pintype "bidirectional"))
    )
    (net (code "299") (name "unconnected-(U2F-DGND50-PadN19)") (class "Default")
      (node (ref "U2") (pin "N19") (pinfunction "DGND50_N19") (pintype "bidirectional"))
    )
    (net (code "300") (name "unconnected-(U2F-DGND51-PadN20)") (class "Default")
      (node (ref "U2") (pin "N20") (pinfunction "DGND51_N20") (pintype "bidirectional"))
    )
    (net (code "301") (name "unconnected-(U2F-DGND52-PadP19)") (class "Default")
      (node (ref "U2") (pin "P19") (pinfunction "DGND52_P19") (pintype "bidirectional"))
    )
    (net (code "302") (name "unconnected-(U2F-DGND53-PadP20)") (class "Default")
      (node (ref "U2") (pin "P20") (pinfunction "DGND53_P20") (pintype "bidirectional"))
    )
    (net (code "303") (name "unconnected-(U2F-DGND54-PadR19)") (class "Default")
      (node (ref "U2") (pin "R19") (pinfunction "DGND54_R19") (pintype "bidirectional"))
    )
    (net (code "304") (name "unconnected-(U2F-DGND55-PadR20)") (class "Default")
      (node (ref "U2") (pin "R20") (pinfunction "DGND55_R20") (pintype "bidirectional"))
    )
    (net (code "305") (name "unconnected-(U2F-DGND56-PadT19)") (class "Default")
      (node (ref "U2") (pin "T19") (pinfunction "DGND56_T19") (pintype "bidirectional"))
    )
    (net (code "306") (name "unconnected-(U2F-DGND57-PadT20)") (class "Default")
      (node (ref "U2") (pin "T20") (pinfunction "DGND57_T20") (pintype "bidirectional"))
    )
    (net (code "307") (name "unconnected-(U2F-DGND58-PadU19)") (class "Default")
      (node (ref "U2") (pin "U19") (pinfunction "DGND58_U19") (pintype "bidirectional"))
    )
    (net (code "308") (name "unconnected-(U2F-DGND60-PadV18)") (class "Default")
      (node (ref "U2") (pin "V18") (pinfunction "DGND60_V18") (pintype "bidirectional"))
    )
    (net (code "309") (name "unconnected-(U2F-DGND63-PadW3)") (class "Default")
      (node (ref "U2") (pin "W3") (pinfunction "DGND63_W3") (pintype "bidirectional"))
    )
    (net (code "310") (name "unconnected-(U2F-DGND65-PadW5)") (class "Default")
      (node (ref "U2") (pin "W5") (pinfunction "DGND65_W5") (pintype "bidirectional"))
    )
    (net (code "311") (name "unconnected-(U2F-DGND66-PadW6)") (class "Default")
      (node (ref "U2") (pin "W6") (pinfunction "DGND66_W6") (pintype "bidirectional"))
    )
    (net (code "312") (name "unconnected-(U2F-DGND67-PadW7)") (class "Default")
      (node (ref "U2") (pin "W7") (pinfunction "DGND67_W7") (pintype "bidirectional"))
    )
    (net (code "313") (name "unconnected-(U2F-DGND68-PadW8)") (class "Default")
      (node (ref "U2") (pin "W8") (pinfunction "DGND68_W8") (pintype "bidirectional"))
    )
    (net (code "314") (name "unconnected-(U2F-DGND69-PadW9)") (class "Default")
      (node (ref "U2") (pin "W9") (pinfunction "DGND69_W9") (pintype "bidirectional"))
    )
    (net (code "315") (name "unconnected-(U2F-DGND70-PadW10)") (class "Default")
      (node (ref "U2") (pin "W10") (pinfunction "DGND70_W10") (pintype "bidirectional"))
    )
    (net (code "316") (name "unconnected-(U2F-DGND72-PadW12)") (class "Default")
      (node (ref "U2") (pin "W12") (pinfunction "DGND72_W12") (pintype "bidirectional"))
    )
    (net (code "317") (name "unconnected-(U2F-DGND73-PadW13)") (class "Default")
      (node (ref "U2") (pin "W13") (pinfunction "DGND73_W13") (pintype "bidirectional"))
    )
    (net (code "318") (name "unconnected-(U2F-DGND74-PadW14)") (class "Default")
      (node (ref "U2") (pin "W14") (pinfunction "DGND74_W14") (pintype "bidirectional"))
    )
    (net (code "319") (name "unconnected-(U2F-DGND75-PadW15)") (class "Default")
      (node (ref "U2") (pin "W15") (pinfunction "DGND75_W15") (pintype "bidirectional"))
    )
    (net (code "320") (name "unconnected-(U2F-DGND76-PadW16)") (class "Default")
      (node (ref "U2") (pin "W16") (pinfunction "DGND76_W16") (pintype "bidirectional"))
    )
    (net (code "321") (name "unconnected-(U2F-DGND77-PadW17)") (class "Default")
      (node (ref "U2") (pin "W17") (pinfunction "DGND77_W17") (pintype "bidirectional"))
    )
    (net (code "322") (name "unconnected-(U2F-DGND78-PadW18)") (class "Default")
      (node (ref "U2") (pin "W18") (pinfunction "DGND78_W18") (pintype "bidirectional"))
    )
    (net (code "323") (name "unconnected-(U2F-DGND79-PadW19)") (class "Default")
      (node (ref "U2") (pin "W19") (pinfunction "DGND79_W19") (pintype "bidirectional"))
    )
    (net (code "324") (name "unconnected-(U2F-DGND82-PadY7)") (class "Default")
      (node (ref "U2") (pin "Y7") (pinfunction "DGND82_Y7") (pintype "bidirectional"))
    )
    (net (code "325") (name "unconnected-(U2F-DGND83-PadY10)") (class "Default")
      (node (ref "U2") (pin "Y10") (pinfunction "DGND83_Y10") (pintype "bidirectional"))
    )
    (net (code "326") (name "unconnected-(U2F-DGND84-PadY12)") (class "Default")
      (node (ref "U2") (pin "Y12") (pinfunction "DGND84_Y12") (pintype "bidirectional"))
    )
    (net (code "327") (name "unconnected-(U2F-DGND85-PadY15)") (class "Default")
      (node (ref "U2") (pin "Y15") (pinfunction "DGND85_Y15") (pintype "bidirectional"))
    )
    (net (code "328") (name "unconnected-(U3-NC-Pad1)") (class "Default")
      (node (ref "U3") (pin "1") (pinfunction "NC_1") (pintype "passive"))
    )
  )
)
